# FW_Toolboard1_v71_Eagle_9.net
KiCad netlist of a schematic drawn in EAGLE
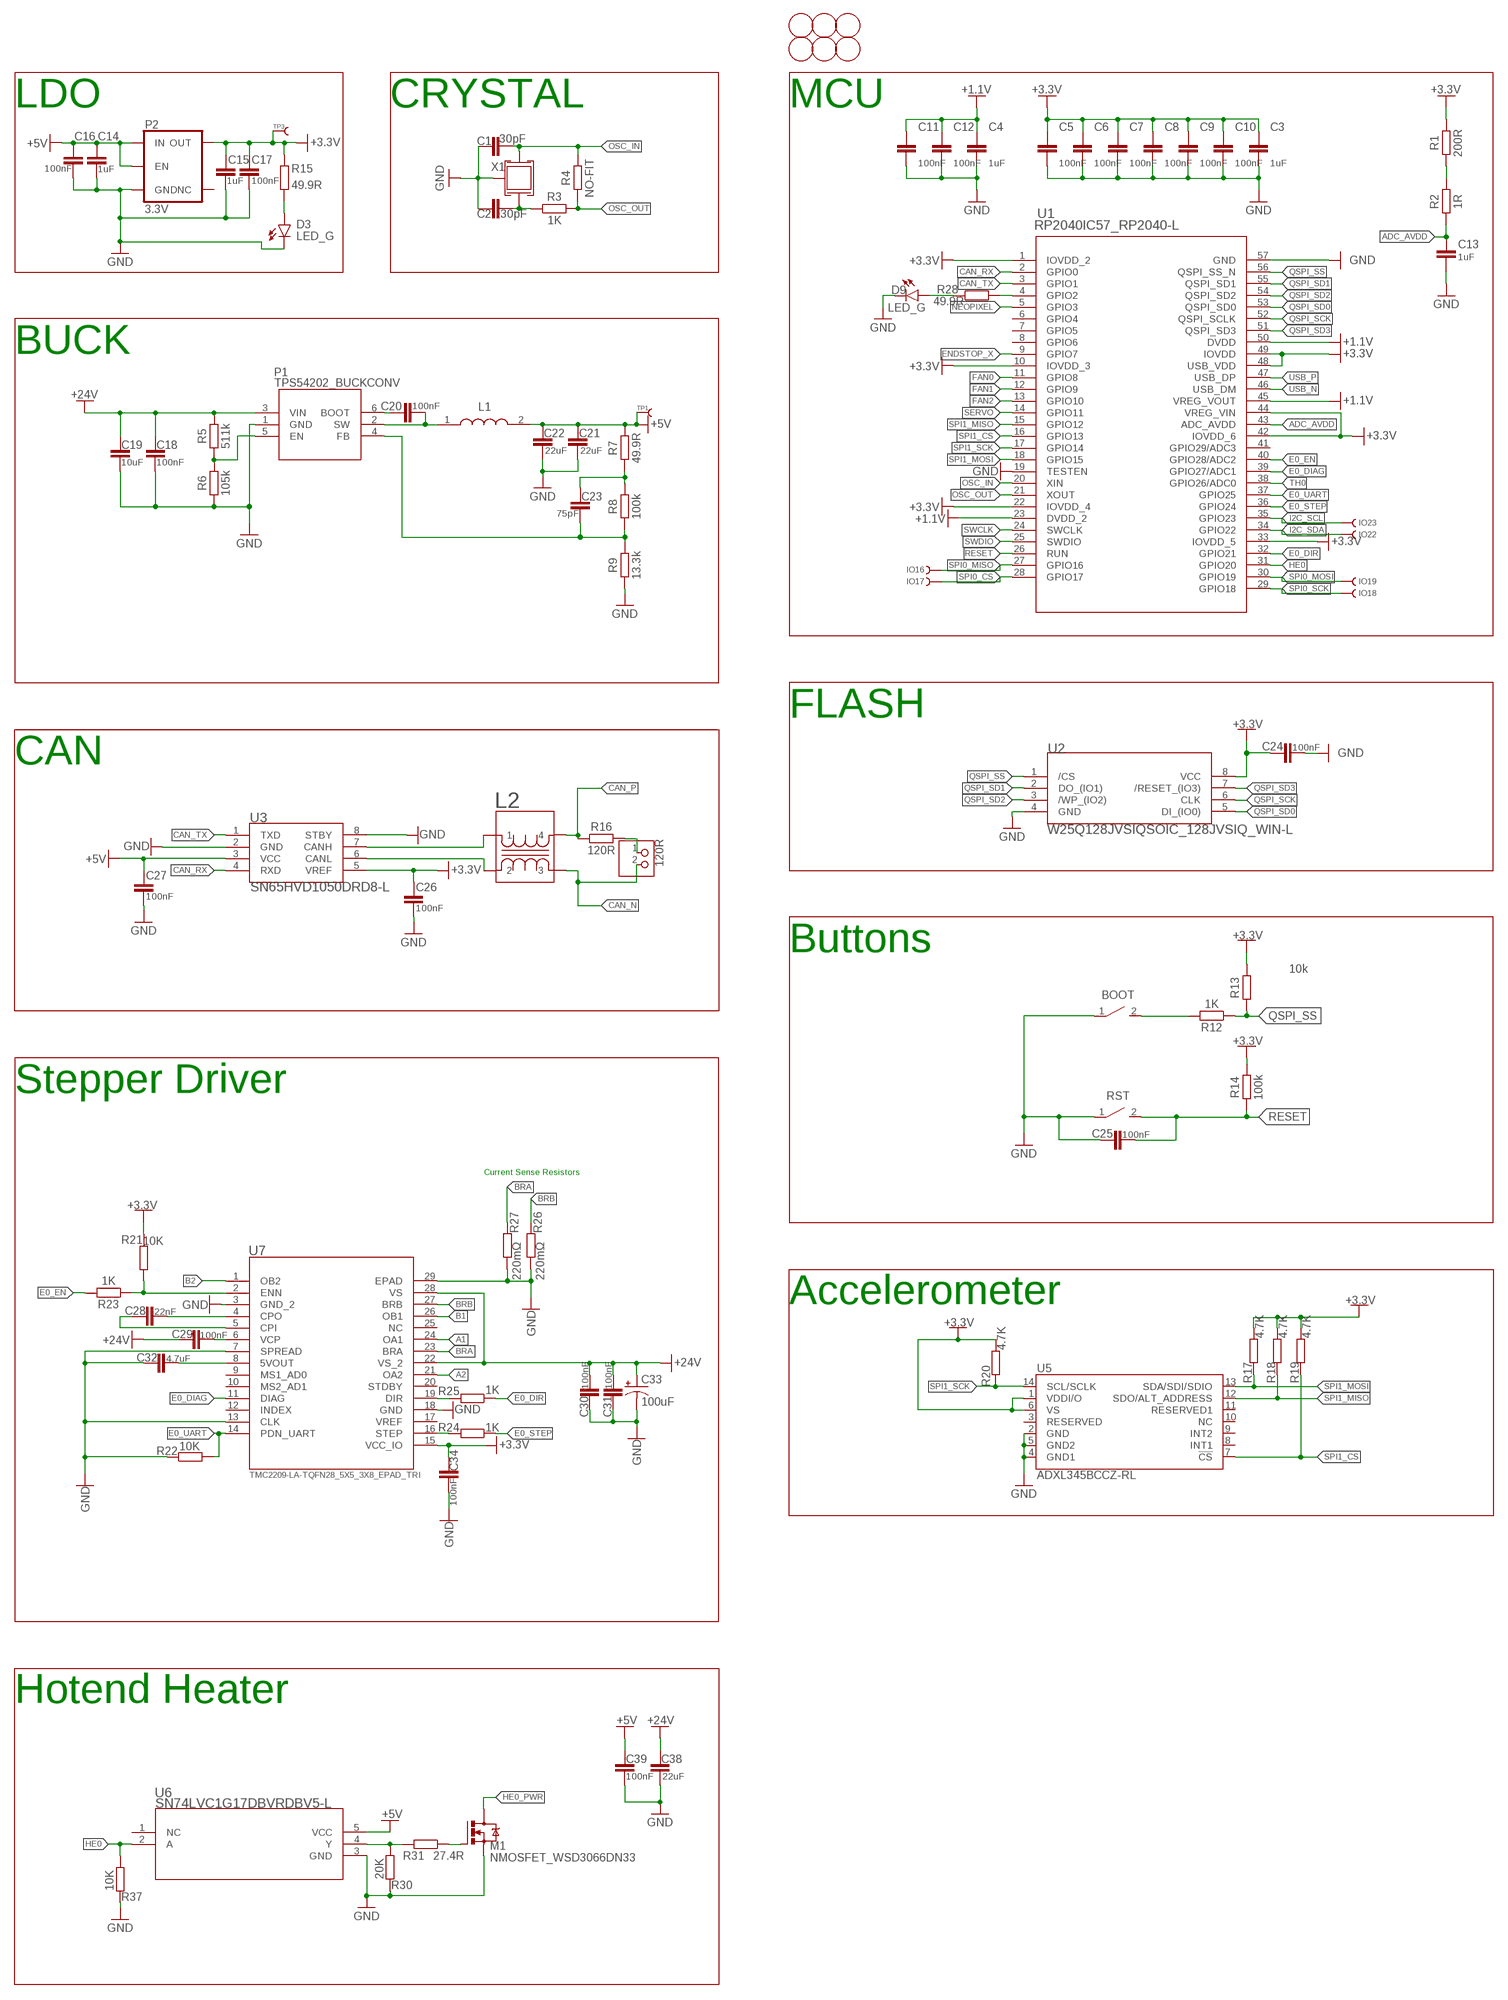
[diagram p0: schematic, sheet 1, part 1 of 2]
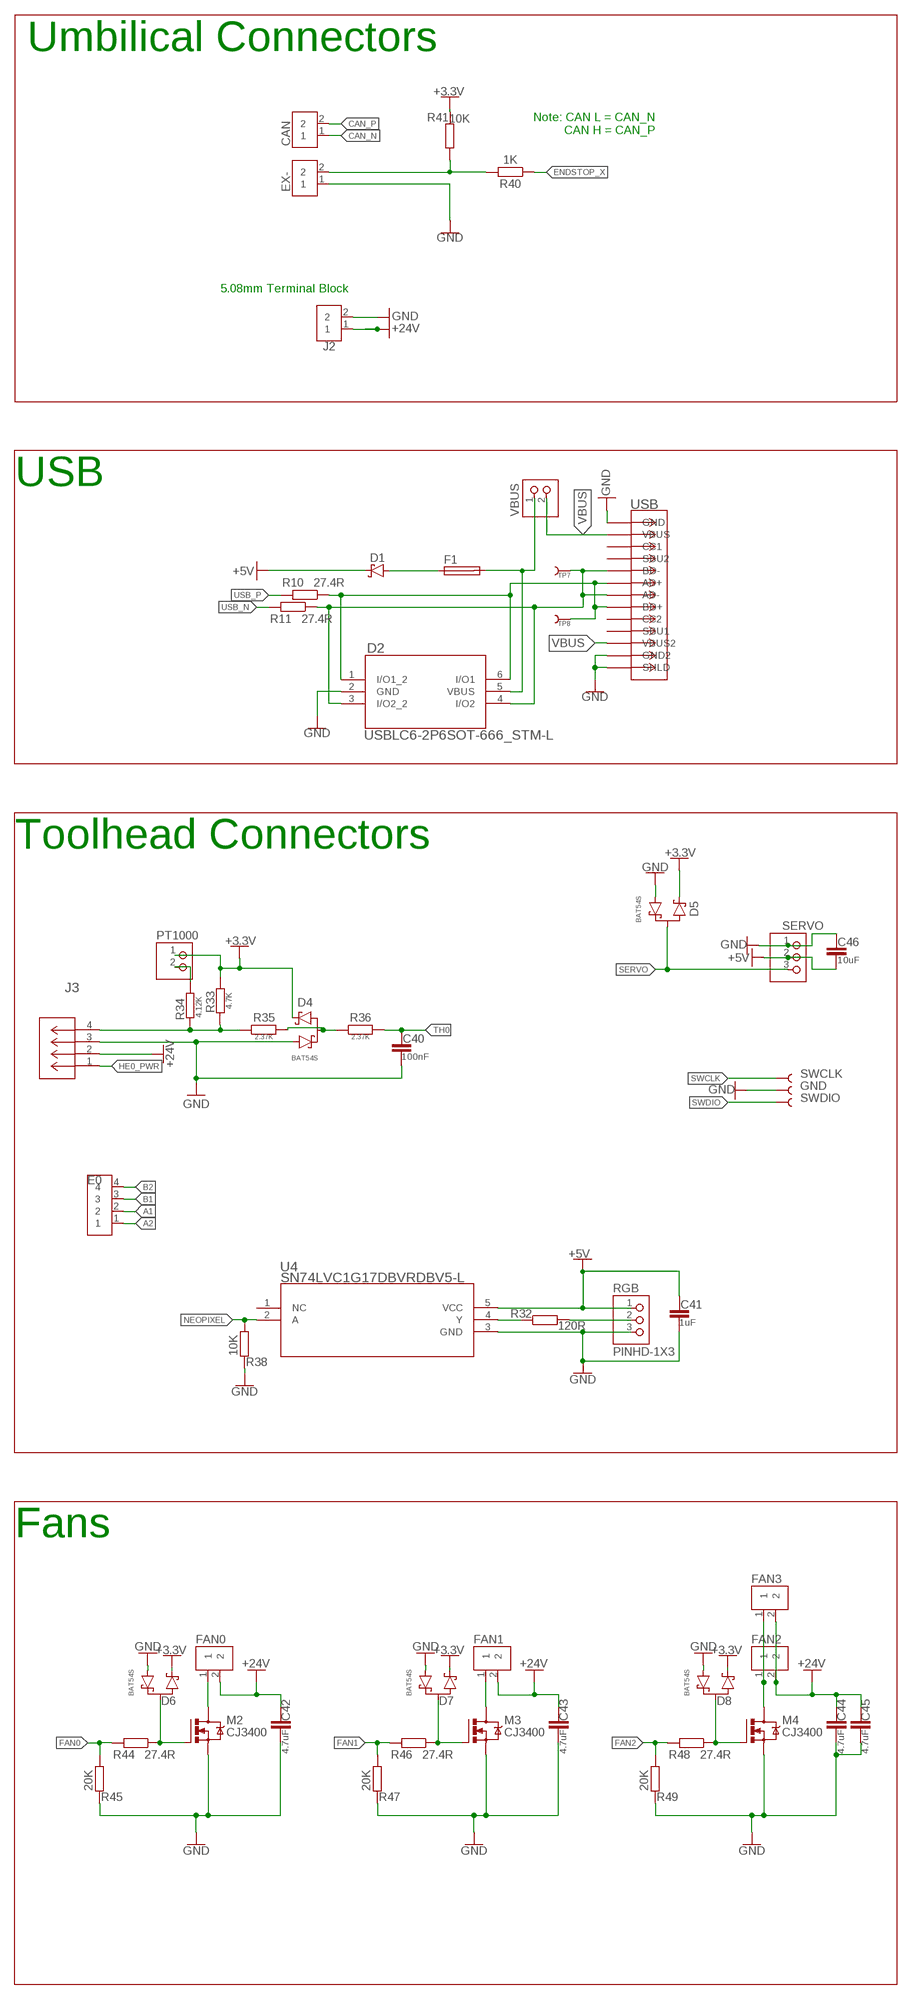
[diagram p1: schematic, sheet 1, part 2 of 2]

(export (version "E")
  (design (tool "Eeschema 10.0.6"))
  (components
    (comp (ref "120R")
      (value "PINHD-1X2")
      (footprint "eagle-import:1X02")
      (libsource (lib "eagle-import") (part "PINHD-1X2"))
    )
    (comp (ref "BOOT")
      (value "B3U-1000P(M)-B")
      (footprint "eagle-import:B3U-1000P(M)-B")
      (fields (field (name "MANUFACTURER") "OMRON"))
      (libsource (lib "eagle-import") (part "B3U-X0001000P(M)-BB3U-1000P(M)-B"))
    )
    (comp (ref "C1")
      (value "30pF")
      (footprint "eagle-import:CAPC1005X60")
      (libsource (lib "eagle-import") (part "CCHIP-0402(1005-METRIC)_"))
    )
    (comp (ref "C2")
      (value "30pF")
      (footprint "eagle-import:CAPC1005X60")
      (libsource (lib "eagle-import") (part "CCHIP-0402(1005-METRIC)_"))
    )
    (comp (ref "C3")
      (value "1uF")
      (footprint "eagle-import:CAPC1005X60")
      (libsource (lib "eagle-import") (part "CCHIP-0402(1005-METRIC)_"))
    )
    (comp (ref "C4")
      (value "1uF")
      (footprint "eagle-import:CAPC1005X60")
      (libsource (lib "eagle-import") (part "CCHIP-0402(1005-METRIC)_"))
    )
    (comp (ref "C5")
      (value "100nF")
      (footprint "eagle-import:CAPC1005X60")
      (libsource (lib "eagle-import") (part "CCHIP-0402(1005-METRIC)_"))
    )
    (comp (ref "C6")
      (value "100nF")
      (footprint "eagle-import:CAPC1005X60")
      (libsource (lib "eagle-import") (part "CCHIP-0402(1005-METRIC)_"))
    )
    (comp (ref "C7")
      (value "100nF")
      (footprint "eagle-import:CAPC1005X60")
      (libsource (lib "eagle-import") (part "CCHIP-0402(1005-METRIC)_"))
    )
    (comp (ref "C8")
      (value "100nF")
      (footprint "eagle-import:CAPC1005X60")
      (libsource (lib "eagle-import") (part "CCHIP-0402(1005-METRIC)_"))
    )
    (comp (ref "C9")
      (value "100nF")
      (footprint "eagle-import:CAPC1005X60")
      (libsource (lib "eagle-import") (part "CCHIP-0402(1005-METRIC)_"))
    )
    (comp (ref "C10")
      (value "100nF")
      (footprint "eagle-import:CAPC1005X60")
      (libsource (lib "eagle-import") (part "CCHIP-0402(1005-METRIC)_"))
    )
    (comp (ref "C11")
      (value "100nF")
      (footprint "eagle-import:CAPC1005X60")
      (libsource (lib "eagle-import") (part "CCHIP-0402(1005-METRIC)_"))
    )
    (comp (ref "C12")
      (value "100nF")
      (footprint "eagle-import:CAPC1005X60")
      (libsource (lib "eagle-import") (part "CCHIP-0402(1005-METRIC)_"))
    )
    (comp (ref "C13")
      (value "1uF")
      (footprint "eagle-import:CAPC1005X60")
      (libsource (lib "eagle-import") (part "CCHIP-0402(1005-METRIC)_"))
    )
    (comp (ref "C14")
      (value "1uF")
      (footprint "eagle-import:CAPC1005X60")
      (libsource (lib "eagle-import") (part "CCHIP-0402(1005-METRIC)_"))
    )
    (comp (ref "C15")
      (value "1uF")
      (footprint "eagle-import:CAPC1005X60")
      (libsource (lib "eagle-import") (part "CCHIP-0402(1005-METRIC)_"))
    )
    (comp (ref "C16")
      (value "100nF")
      (footprint "eagle-import:CAPC1005X60")
      (libsource (lib "eagle-import") (part "CCHIP-0402(1005-METRIC)_"))
    )
    (comp (ref "C17")
      (value "100nF")
      (footprint "eagle-import:CAPC1005X60")
      (libsource (lib "eagle-import") (part "CCHIP-0402(1005-METRIC)_"))
    )
    (comp (ref "C18")
      (value "100nF")
      (footprint "eagle-import:CAPC1005X60")
      (libsource (lib "eagle-import") (part "CCHIP-0402(1005-METRIC)_"))
    )
    (comp (ref "C19")
      (value "10uF")
      (footprint "eagle-import:CAPC1608X85")
      (libsource (lib "eagle-import") (part "CCHIP-0603(1608-METRIC)_"))
    )
    (comp (ref "C20")
      (value "100nF")
      (footprint "eagle-import:CAPC1005X60")
      (libsource (lib "eagle-import") (part "CCHIP-0402(1005-METRIC)_"))
    )
    (comp (ref "C21")
      (value "22uF")
      (footprint "eagle-import:CAPC2012X110")
      (libsource (lib "eagle-import") (part "CCHIP-0805(2012-METRIC)_"))
    )
    (comp (ref "C22")
      (value "22uF")
      (footprint "eagle-import:CAPC2012X110")
      (libsource (lib "eagle-import") (part "CCHIP-0805(2012-METRIC)_"))
    )
    (comp (ref "C23")
      (value "75pF")
      (footprint "eagle-import:CAPC1005X60")
      (libsource (lib "eagle-import") (part "CCHIP-0402(1005-METRIC)_"))
    )
    (comp (ref "C24")
      (value "100nF")
      (footprint "eagle-import:CAPC1005X60")
      (libsource (lib "eagle-import") (part "CCHIP-0402(1005-METRIC)_"))
    )
    (comp (ref "C25")
      (value "100nF")
      (footprint "eagle-import:CAPC1005X60")
      (libsource (lib "eagle-import") (part "CCHIP-0402(1005-METRIC)_"))
    )
    (comp (ref "C26")
      (value "100nF")
      (footprint "eagle-import:CAPC1005X60")
      (libsource (lib "eagle-import") (part "CCHIP-0402(1005-METRIC)_"))
    )
    (comp (ref "C27")
      (value "100nF")
      (footprint "eagle-import:CAPC1005X60")
      (libsource (lib "eagle-import") (part "CCHIP-0402(1005-METRIC)_"))
    )
    (comp (ref "C28")
      (value "22nF")
      (footprint "eagle-import:CAPC1005X60")
      (libsource (lib "eagle-import") (part "CCHIP-0402(1005-METRIC)_"))
    )
    (comp (ref "C29")
      (value "100nF")
      (footprint "eagle-import:CAPC1005X60")
      (libsource (lib "eagle-import") (part "CCHIP-0402(1005-METRIC)_"))
    )
    (comp (ref "C30")
      (value "100nF")
      (footprint "eagle-import:CAPC1005X60")
      (libsource (lib "eagle-import") (part "CCHIP-0402(1005-METRIC)_"))
    )
    (comp (ref "C31")
      (value "100nF")
      (footprint "eagle-import:CAPC1005X60")
      (libsource (lib "eagle-import") (part "CCHIP-0402(1005-METRIC)_"))
    )
    (comp (ref "C32")
      (value "4.7uF")
      (footprint "eagle-import:CAPC1608X85")
      (libsource (lib "eagle-import") (part "CCHIP-0603(1608-METRIC)_"))
    )
    (comp (ref "C33")
      (value "100uF")
      (footprint "eagle-import:PANASONIC_D")
      (libsource (lib "eagle-import") (part "100UF-POLAR-25V-20%(ELEC)"))
    )
    (comp (ref "C34")
      (value "100nF")
      (footprint "eagle-import:CAPC1005X60")
      (libsource (lib "eagle-import") (part "CCHIP-0402(1005-METRIC)_"))
    )
    (comp (ref "C38")
      (value "22uF")
      (footprint "eagle-import:CAPC2012X110")
      (libsource (lib "eagle-import") (part "CCHIP-0805(2012-METRIC)_"))
    )
    (comp (ref "C39")
      (value "100nF")
      (footprint "eagle-import:CAPC1005X60")
      (libsource (lib "eagle-import") (part "CCHIP-0402(1005-METRIC)_"))
    )
    (comp (ref "C40")
      (value "100nF")
      (footprint "eagle-import:CAPC1005X60")
      (libsource (lib "eagle-import") (part "CCHIP-0402(1005-METRIC)_"))
    )
    (comp (ref "C41")
      (value "1uF")
      (footprint "eagle-import:CAPC1005X60")
      (libsource (lib "eagle-import") (part "CCHIP-0402(1005-METRIC)_"))
    )
    (comp (ref "C42")
      (value "4.7uF")
      (footprint "eagle-import:CAPC1608X85")
      (libsource (lib "eagle-import") (part "CCHIP-0603(1608-METRIC)_"))
    )
    (comp (ref "C43")
      (value "4.7uF")
      (footprint "eagle-import:CAPC1608X85")
      (libsource (lib "eagle-import") (part "CCHIP-0603(1608-METRIC)_"))
    )
    (comp (ref "C44")
      (value "4.7uF")
      (footprint "eagle-import:CAPC1608X85")
      (libsource (lib "eagle-import") (part "CCHIP-0603(1608-METRIC)_"))
    )
    (comp (ref "C45")
      (value "4.7uF")
      (footprint "eagle-import:CAPC1608X85")
      (libsource (lib "eagle-import") (part "CCHIP-0603(1608-METRIC)_"))
    )
    (comp (ref "C46")
      (value "10uF")
      (footprint "eagle-import:CAPC1608X85")
      (libsource (lib "eagle-import") (part "CCHIP-0603(1608-METRIC)_"))
    )
    (comp (ref "CAN")
      (value "3A/250V")
      (footprint "eagle-import:S2B-XH-A")
      (fields
        (field (name "DIGIKEY_PART_NUMBER") "455-2257-ND")
        (field (name "MANUFACTURER") "JST Sales America Inc.")
        (field (name "MPN") "S2B-XH-A(LF)(SN)")
        (field (name "CREATED_BY") "PCBLayout.com")
      )
      (libsource (lib "eagle-import") (part "S2B-XH-A"))
    )
    (comp (ref "D1")
      (value "MBR0520LT1G")
      (footprint "eagle-import:SODFL3718X115")
      (fields (field (name "MANUFACTURER") "ON Semiconductor"))
      (libsource (lib "eagle-import") (part "SCHOTTKY_DO-219MBR0520LT1G"))
    )
    (comp (ref "D2")
      (value "USBLC6-2P6SOT-666_STM-L")
      (footprint "eagle-import:SOT-666_STM-L")
      (fields
        (field (name "MANUFACTURER_PART_NUMBER") "USBLC6-2P6")
        (field (name "COPYRIGHT") "Copyright (C) 2023 Ultra Librarian. All rights reserved.")
      )
      (libsource (lib "eagle-import") (part "USBLC6-2P6SOT-666_STM-L"))
    )
    (comp (ref "D3")
      (value "LED_G")
      (footprint "eagle-import:LEDC1608X35N_FLAT-G")
      (libsource (lib "eagle-import") (part "CHIP-FLAT-G_0603-0.35MM"))
    )
    (comp (ref "D4")
      (value "BAT54S")
      (footprint "eagle-import:SOT23")
      (libsource (lib "eagle-import") (part "BAT54S"))
    )
    (comp (ref "D5")
      (value "BAT54S")
      (footprint "eagle-import:SOT23")
      (libsource (lib "eagle-import") (part "BAT54S"))
    )
    (comp (ref "D6")
      (value "BAT54S")
      (footprint "eagle-import:SOT23")
      (libsource (lib "eagle-import") (part "BAT54S"))
    )
    (comp (ref "D7")
      (value "BAT54S")
      (footprint "eagle-import:SOT23")
      (libsource (lib "eagle-import") (part "BAT54S"))
    )
    (comp (ref "D8")
      (value "BAT54S")
      (footprint "eagle-import:SOT23")
      (libsource (lib "eagle-import") (part "BAT54S"))
    )
    (comp (ref "D9")
      (value "LED_G")
      (footprint "eagle-import:LEDC1608X35N_FLAT-G")
      (libsource (lib "eagle-import") (part "CHIP-FLAT-G_0603-0.35MM"))
    )
    (comp (ref "E0")
      (value "3A/250V")
      (footprint "eagle-import:S4B-XH-A")
      (fields (field (name "MANUFACTURER") "JST Sales America Inc. ") (field (name "MPN") "S4B-XH-A(LF)(SN)"))
      (libsource (lib "eagle-import") (part "S4B-XH-A"))
    )
    (comp (ref "EX-")
      (value "3A/250V")
      (footprint "eagle-import:S2B-XH-A")
      (fields
        (field (name "DIGIKEY_PART_NUMBER") "455-2257-ND")
        (field (name "MANUFACTURER") "JST Sales America Inc.")
        (field (name "MPN") "S2B-XH-A(LF)(SN)")
        (field (name "CREATED_BY") "PCBLayout.com")
      )
      (libsource (lib "eagle-import") (part "S2B-XH-A"))
    )
    (comp (ref "F1")
      (value "FUSE_CHIP-0603(1608-METRIC)")
      (footprint "eagle-import:FUSC1608X60N")
      (libsource (lib "eagle-import") (part "FUSECHIP-0603(1608-METRIC)_"))
    )
    (comp (ref "FAN0")
      (value "3A/250V")
      (footprint "eagle-import:S2B-XH-A")
      (fields
        (field (name "DIGIKEY_PART_NUMBER") "455-2257-ND")
        (field (name "MANUFACTURER") "JST Sales America Inc.")
        (field (name "MPN") "S2B-XH-A(LF)(SN)")
        (field (name "CREATED_BY") "PCBLayout.com")
      )
      (libsource (lib "eagle-import") (part "S2B-XH-A"))
    )
    (comp (ref "FAN1")
      (value "3A/250V")
      (footprint "eagle-import:S2B-XH-A")
      (fields
        (field (name "DIGIKEY_PART_NUMBER") "455-2257-ND")
        (field (name "MANUFACTURER") "JST Sales America Inc.")
        (field (name "MPN") "S2B-XH-A(LF)(SN)")
        (field (name "CREATED_BY") "PCBLayout.com")
      )
      (libsource (lib "eagle-import") (part "S2B-XH-A"))
    )
    (comp (ref "FAN2")
      (value "3A/250V")
      (footprint "eagle-import:S2B-XH-A")
      (fields
        (field (name "DIGIKEY_PART_NUMBER") "455-2257-ND")
        (field (name "MANUFACTURER") "JST Sales America Inc.")
        (field (name "MPN") "S2B-XH-A(LF)(SN)")
        (field (name "CREATED_BY") "PCBLayout.com")
      )
      (libsource (lib "eagle-import") (part "S2B-XH-A"))
    )
    (comp (ref "FAN3")
      (value "3A/250V")
      (footprint "eagle-import:S2B-XH-A")
      (fields
        (field (name "DIGIKEY_PART_NUMBER") "455-2257-ND")
        (field (name "MANUFACTURER") "JST Sales America Inc.")
        (field (name "MPN") "S2B-XH-A(LF)(SN)")
        (field (name "CREATED_BY") "PCBLayout.com")
      )
      (libsource (lib "eagle-import") (part "S2B-XH-A"))
    )
    (comp (ref "FD1")
      (value "FIDUCIAL")
      (footprint "eagle-import:FIDUCIAL_1MM")
      (libsource (lib "eagle-import") (part "FIDUCIAL"))
    )
    (comp (ref "FD2")
      (value "FIDUCIAL")
      (footprint "eagle-import:FIDUCIAL_1MM")
      (libsource (lib "eagle-import") (part "FIDUCIAL"))
    )
    (comp (ref "FD3")
      (value "FIDUCIAL")
      (footprint "eagle-import:FIDUCIAL_1MM")
      (libsource (lib "eagle-import") (part "FIDUCIAL"))
    )
    (comp (ref "FD4")
      (value "FIDUCIAL")
      (footprint "eagle-import:FIDUCIAL_1MM")
      (libsource (lib "eagle-import") (part "FIDUCIAL"))
    )
    (comp (ref "FD5")
      (value "FIDUCIAL")
      (footprint "eagle-import:FIDUCIAL_1MM")
      (libsource (lib "eagle-import") (part "FIDUCIAL"))
    )
    (comp (ref "FD6")
      (value "FIDUCIAL")
      (footprint "eagle-import:FIDUCIAL_1MM")
      (libsource (lib "eagle-import") (part "FIDUCIAL"))
    )
    (comp (ref "GND")
      (value "TEST-POINT3X4")
      (footprint "eagle-import:PAD.03X.04")
      (libsource (lib "eagle-import") (part "SparkFun-Connectors_513_TEST-POINT3X4"))
    )
    (comp (ref "IO16")
      (value "TEST-POINT3")
      (footprint "eagle-import:PAD.03X.03")
      (libsource (lib "eagle-import") (part "SparkFun-Connectors_513_TEST-POINT3"))
    )
    (comp (ref "IO17")
      (value "TEST-POINT3")
      (footprint "eagle-import:PAD.03X.03")
      (libsource (lib "eagle-import") (part "SparkFun-Connectors_513_TEST-POINT3"))
    )
    (comp (ref "IO18")
      (value "TEST-POINT3")
      (footprint "eagle-import:PAD.03X.03")
      (libsource (lib "eagle-import") (part "SparkFun-Connectors_513_TEST-POINT3"))
    )
    (comp (ref "IO19")
      (value "TEST-POINT3")
      (footprint "eagle-import:PAD.03X.03")
      (libsource (lib "eagle-import") (part "SparkFun-Connectors_513_TEST-POINT3"))
    )
    (comp (ref "IO22")
      (value "TEST-POINT3")
      (footprint "eagle-import:PAD.03X.03")
      (libsource (lib "eagle-import") (part "SparkFun-Connectors_513_TEST-POINT3"))
    )
    (comp (ref "IO23")
      (value "TEST-POINT3")
      (footprint "eagle-import:PAD.03X.03")
      (libsource (lib "eagle-import") (part "SparkFun-Connectors_513_TEST-POINT3"))
    )
    (comp (ref "J2")
      (value "2828XX-2282837-2")
      (footprint "eagle-import:TERMBLK_508-2N")
      (fields (field (name "MANUFACTURER") "TE Connectivity") (field (name "MPN") "282837-2"))
      (libsource (lib "eagle-import") (part "2828XX-2282837-2"))
    )
    (comp (ref "J3")
      (value "430450400CON_430450400_MOL")
      (footprint "eagle-import:CON_430450400_MOL")
      (fields
        (field (name "MANUFACTURER_PART_NUMBER") "430450400")
        (field (name "COPYRIGHT") "Copyright (C) 2023 Ultra Librarian. All rights reserved.")
      )
      (libsource (lib "eagle-import") (part "430450400CON_430450400_MOL"))
    )
    (comp (ref "L1")
      (value "ASPI-0630HI-100M-T157X7X4")
      (footprint "eagle-import:SMDRI74-680MT")
      (libsource (lib "eagle-import") (part "ASPI-0630HI-100M-T157X7X4"))
    )
    (comp (ref "L2")
      (value "ACM2012-201-2P-T002ACM2012_TDK")
      (footprint "eagle-import:ACM2012_TDK")
      (fields
        (field (name "MANUFACTURER_PART_NUMBER") "ACM2012-201-2P-T002")
        (field (name "COPYRIGHT") "Copyright (C) 2023 Ultra Librarian. All rights reserved.")
      )
      (libsource (lib "eagle-import") (part "ACM2012-201-2P-T002ACM2012_TDK"))
    )
    (comp (ref "M1")
      (value "NMOSFET_WSD3066DN33")
      (footprint "eagle-import:NMOSFET_WSD3066DN33")
      (libsource (lib "eagle-import") (part "NMOSFET_WSD3066DN33"))
    )
    (comp (ref "M2")
      (value "CJ3400")
      (footprint "eagle-import:SOT23")
      (fields (field (name "MANUFACTURER") "ON Semiconductor") (field (name "MPN") "BSS123L"))
      (libsource (lib "eagle-import") (part "NMOSFET__SOT23-GSDBSS123"))
    )
    (comp (ref "M3")
      (value "CJ3400")
      (footprint "eagle-import:SOT23")
      (fields (field (name "MANUFACTURER") "ON Semiconductor") (field (name "MPN") "BSS123L"))
      (libsource (lib "eagle-import") (part "NMOSFET__SOT23-GSDBSS123"))
    )
    (comp (ref "M4")
      (value "CJ3400")
      (footprint "eagle-import:SOT23")
      (fields (field (name "MANUFACTURER") "ON Semiconductor") (field (name "MPN") "BSS123L"))
      (libsource (lib "eagle-import") (part "NMOSFET__SOT23-GSDBSS123"))
    )
    (comp (ref "P1")
      (value "TPS54202_BUCKCONV")
      (footprint "eagle-import:SOT-23-6")
      (libsource (lib "eagle-import") (part "TPS54202_BUCKCONV"))
    )
    (comp (ref "P2")
      (value "3.3V")
      (footprint "eagle-import:SOT23-5")
      (libsource (lib "eagle-import") (part "V_REG_AP2112K-3.3V"))
    )
    (comp (ref "PT1000")
      (value "PINHD-1X2")
      (footprint "eagle-import:1X02")
      (libsource (lib "eagle-import") (part "PINHD-1X2"))
    )
    (comp (ref "R1")
      (value "200R")
      (footprint "eagle-import:RESC1005X40")
      (libsource (lib "eagle-import") (part "RCHIP-0402(1005-METRIC)_"))
    )
    (comp (ref "R2")
      (value "1R")
      (footprint "eagle-import:RESC1005X40")
      (libsource (lib "eagle-import") (part "RCHIP-0402(1005-METRIC)_"))
    )
    (comp (ref "R3")
      (value "1K")
      (footprint "eagle-import:RESC1005X40")
      (libsource (lib "eagle-import") (part "RCHIP-0402(1005-METRIC)_"))
    )
    (comp (ref "R4")
      (value "NO-FIT")
      (footprint "eagle-import:RESC1005X40")
      (libsource (lib "eagle-import") (part "RCHIP-0402(1005-METRIC)_"))
    )
    (comp (ref "R5")
      (value "511k")
      (footprint "eagle-import:RESC1005X40")
      (libsource (lib "eagle-import") (part "RCHIP-0402(1005-METRIC)_"))
    )
    (comp (ref "R6")
      (value "105k")
      (footprint "eagle-import:RESC1005X40")
      (libsource (lib "eagle-import") (part "RCHIP-0402(1005-METRIC)_"))
    )
    (comp (ref "R7")
      (value "49.9R")
      (footprint "eagle-import:RESC1005X40")
      (libsource (lib "eagle-import") (part "RCHIP-0402(1005-METRIC)_"))
    )
    (comp (ref "R8")
      (value "100k")
      (footprint "eagle-import:RESC1005X40")
      (libsource (lib "eagle-import") (part "RCHIP-0402(1005-METRIC)_"))
    )
    (comp (ref "R9")
      (value "13.3k")
      (footprint "eagle-import:RESC1005X40")
      (libsource (lib "eagle-import") (part "RCHIP-0402(1005-METRIC)_"))
    )
    (comp (ref "R10")
      (value "27.4R")
      (footprint "eagle-import:RESC1005X40")
      (libsource (lib "eagle-import") (part "RCHIP-0402(1005-METRIC)_"))
    )
    (comp (ref "R11")
      (value "27.4R")
      (footprint "eagle-import:RESC1005X40")
      (libsource (lib "eagle-import") (part "RCHIP-0402(1005-METRIC)_"))
    )
    (comp (ref "R12")
      (value "1K")
      (footprint "eagle-import:RESC1005X40")
      (libsource (lib "eagle-import") (part "RCHIP-0402(1005-METRIC)_"))
    )
    (comp (ref "R13")
      (value "10k")
      (footprint "eagle-import:RESC1005X40")
      (libsource (lib "eagle-import") (part "RCHIP-0402(1005-METRIC)_"))
    )
    (comp (ref "R14")
      (value "100k")
      (footprint "eagle-import:RESC1005X40")
      (libsource (lib "eagle-import") (part "RCHIP-0402(1005-METRIC)_"))
    )
    (comp (ref "R15")
      (value "49.9R")
      (footprint "eagle-import:RESC1005X40")
      (libsource (lib "eagle-import") (part "RCHIP-0402(1005-METRIC)_"))
    )
    (comp (ref "R16")
      (value "120R")
      (footprint "eagle-import:RESC1005X40")
      (libsource (lib "eagle-import") (part "RCHIP-0402(1005-METRIC)_"))
    )
    (comp (ref "R17")
      (value "4.7K")
      (footprint "eagle-import:RESC1005X40")
      (libsource (lib "eagle-import") (part "RCHIP-0402(1005-METRIC)_"))
    )
    (comp (ref "R18")
      (value "4.7K")
      (footprint "eagle-import:RESC1005X40")
      (libsource (lib "eagle-import") (part "RCHIP-0402(1005-METRIC)_"))
    )
    (comp (ref "R19")
      (value "4.7K")
      (footprint "eagle-import:RESC1005X40")
      (libsource (lib "eagle-import") (part "RCHIP-0402(1005-METRIC)_"))
    )
    (comp (ref "R20")
      (value "4.7K")
      (footprint "eagle-import:RESC1005X40")
      (libsource (lib "eagle-import") (part "RCHIP-0402(1005-METRIC)_"))
    )
    (comp (ref "R21")
      (value "10K")
      (footprint "eagle-import:RESC1005X40")
      (libsource (lib "eagle-import") (part "RCHIP-0402(1005-METRIC)_"))
    )
    (comp (ref "R22")
      (value "10K")
      (footprint "eagle-import:RESC1005X40")
      (libsource (lib "eagle-import") (part "RCHIP-0402(1005-METRIC)_"))
    )
    (comp (ref "R23")
      (value "1K")
      (footprint "eagle-import:RESC1005X40")
      (libsource (lib "eagle-import") (part "RCHIP-0402(1005-METRIC)_"))
    )
    (comp (ref "R24")
      (value "1K")
      (footprint "eagle-import:RESC1005X40")
      (libsource (lib "eagle-import") (part "RCHIP-0402(1005-METRIC)_"))
    )
    (comp (ref "R25")
      (value "1K")
      (footprint "eagle-import:RESC1005X40")
      (libsource (lib "eagle-import") (part "RCHIP-0402(1005-METRIC)_"))
    )
    (comp (ref "R26")
      (value "220mΩ")
      (footprint "eagle-import:RESC1005X40")
      (libsource (lib "eagle-import") (part "RCHIP-0402(1005-METRIC)_"))
    )
    (comp (ref "R27")
      (value "220mΩ")
      (footprint "eagle-import:RESC1005X40")
      (libsource (lib "eagle-import") (part "RCHIP-0402(1005-METRIC)_"))
    )
    (comp (ref "R28")
      (value "49.9R")
      (footprint "eagle-import:RESC1005X40")
      (libsource (lib "eagle-import") (part "RCHIP-0402(1005-METRIC)_"))
    )
    (comp (ref "R30")
      (value "20K")
      (footprint "eagle-import:RESC1005X40")
      (libsource (lib "eagle-import") (part "RCHIP-0402(1005-METRIC)_"))
    )
    (comp (ref "R31")
      (value "27.4R")
      (footprint "eagle-import:RESC1005X40")
      (libsource (lib "eagle-import") (part "RCHIP-0402(1005-METRIC)_"))
    )
    (comp (ref "R32")
      (value "120R")
      (footprint "eagle-import:RESC1005X40")
      (libsource (lib "eagle-import") (part "RCHIP-0402(1005-METRIC)_"))
    )
    (comp (ref "R33")
      (value "4.7K")
      (footprint "eagle-import:RESC1005X40")
      (libsource (lib "eagle-import") (part "RCHIP-0402(1005-METRIC)_"))
    )
    (comp (ref "R34")
      (value "4.12K")
      (footprint "eagle-import:RESC1005X40")
      (libsource (lib "eagle-import") (part "RCHIP-0402(1005-METRIC)_"))
    )
    (comp (ref "R35")
      (value "2.37K")
      (footprint "eagle-import:RESC1005X40")
      (libsource (lib "eagle-import") (part "RCHIP-0402(1005-METRIC)_"))
    )
    (comp (ref "R36")
      (value "2.37K")
      (footprint "eagle-import:RESC1005X40")
      (libsource (lib "eagle-import") (part "RCHIP-0402(1005-METRIC)_"))
    )
    (comp (ref "R37")
      (value "10K")
      (footprint "eagle-import:RESC1005X40")
      (libsource (lib "eagle-import") (part "RCHIP-0402(1005-METRIC)_"))
    )
    (comp (ref "R38")
      (value "10K")
      (footprint "eagle-import:RESC1005X40")
      (libsource (lib "eagle-import") (part "RCHIP-0402(1005-METRIC)_"))
    )
    (comp (ref "R40")
      (value "1K")
      (footprint "eagle-import:RESC1005X40")
      (libsource (lib "eagle-import") (part "RCHIP-0402(1005-METRIC)_"))
    )
    (comp (ref "R41")
      (value "10K")
      (footprint "eagle-import:RESC1005X40")
      (libsource (lib "eagle-import") (part "RCHIP-0402(1005-METRIC)_"))
    )
    (comp (ref "R44")
      (value "27.4R")
      (footprint "eagle-import:RESC1005X40")
      (libsource (lib "eagle-import") (part "RCHIP-0402(1005-METRIC)_"))
    )
    (comp (ref "R45")
      (value "20K")
      (footprint "eagle-import:RESC1005X40")
      (libsource (lib "eagle-import") (part "RCHIP-0402(1005-METRIC)_"))
    )
    (comp (ref "R46")
      (value "27.4R")
      (footprint "eagle-import:RESC1005X40")
      (libsource (lib "eagle-import") (part "RCHIP-0402(1005-METRIC)_"))
    )
    (comp (ref "R47")
      (value "20K")
      (footprint "eagle-import:RESC1005X40")
      (libsource (lib "eagle-import") (part "RCHIP-0402(1005-METRIC)_"))
    )
    (comp (ref "R48")
      (value "27.4R")
      (footprint "eagle-import:RESC1005X40")
      (libsource (lib "eagle-import") (part "RCHIP-0402(1005-METRIC)_"))
    )
    (comp (ref "R49")
      (value "20K")
      (footprint "eagle-import:RESC1005X40")
      (libsource (lib "eagle-import") (part "RCHIP-0402(1005-METRIC)_"))
    )
    (comp (ref "RGB")
      (value "PINHD-1X3")
      (footprint "eagle-import:1X03")
      (libsource (lib "eagle-import") (part "PINHD-1X3"))
    )
    (comp (ref "RST")
      (value "B3U-1000P(M)-B")
      (footprint "eagle-import:B3U-1000P(M)-B")
      (fields (field (name "MANUFACTURER") "OMRON"))
      (libsource (lib "eagle-import") (part "B3U-X0001000P(M)-BB3U-1000P(M)-B"))
    )
    (comp (ref "SERVO")
      (value "PINHD-1X3")
      (footprint "eagle-import:1X03")
      (libsource (lib "eagle-import") (part "PINHD-1X3"))
    )
    (comp (ref "SWCLK")
      (value "TEST-POINT3X4")
      (footprint "eagle-import:PAD.03X.04")
      (libsource (lib "eagle-import") (part "SparkFun-Connectors_513_TEST-POINT3X4"))
    )
    (comp (ref "SWDIO")
      (value "TEST-POINT3X4")
      (footprint "eagle-import:PAD.03X.04")
      (libsource (lib "eagle-import") (part "SparkFun-Connectors_513_TEST-POINT3X4"))
    )
    (comp (ref "TP1")
      (value "TEST-POINT3")
      (footprint "eagle-import:PAD.012X.012")
      (libsource (lib "eagle-import") (part "TEST-POINT3"))
    )
    (comp (ref "TP3")
      (value "TEST-POINT3")
      (footprint "eagle-import:PAD.012X.012")
      (libsource (lib "eagle-import") (part "TEST-POINT3"))
    )
    (comp (ref "TP7")
      (value "TEST-POINT3")
      (footprint "eagle-import:PAD.012X.012")
      (libsource (lib "eagle-import") (part "TEST-POINT3"))
    )
    (comp (ref "TP8")
      (value "TEST-POINT3")
      (footprint "eagle-import:PAD.012X.012")
      (libsource (lib "eagle-import") (part "TEST-POINT3"))
    )
    (comp (ref "U1")
      (value "RP2040IC57_RP2040-L")
      (footprint "eagle-import:IC57_RP2040-L")
      (fields
        (field (name "MANUFACTURER_PART_NUMBER") "RP2040")
        (field (name "COPYRIGHT") "Copyright (C) 2023 Ultra Librarian. All rights reserved.")
      )
      (libsource (lib "eagle-import") (part "RP2040IC57_RP2040-L"))
    )
    (comp (ref "U2")
      (value "W25Q128JVSIQSOIC_128JVSIQ_WIN-L")
      (footprint "eagle-import:SOIC_128JVSIQ_WIN-L")
      (fields
        (field (name "MANUFACTURER_PART_NUMBER") "W25Q128JVSIQ")
        (field (name "COPYRIGHT") "Copyright (C) 2023 Ultra Librarian. All rights reserved.")
      )
      (libsource (lib "eagle-import") (part "W25Q128JVSIQSOIC_128JVSIQ_WIN-L"))
    )
    (comp (ref "U3")
      (value "SN65HVD1050DRD8-L")
      (footprint "eagle-import:D8-L")
      (fields
        (field (name "MANUFACTURER_PART_NUMBER") "SN65HVD1050DR")
        (field (name "COPYRIGHT") "Copyright (C) 2023 Ultra Librarian. All rights reserved.")
      )
      (libsource (lib "eagle-import") (part "SN65HVD1050DRD8-L"))
    )
    (comp (ref "U4")
      (value "SN74LVC1G17DBVRDBV5-L")
      (footprint "eagle-import:DBV5-L")
      (fields
        (field (name "MANUFACTURER_PART_NUMBER") "SN74LVC1G17DBVR")
        (field (name "COPYRIGHT") "Copyright (C) 2023 Ultra Librarian. All rights reserved.")
      )
      (libsource (lib "eagle-import") (part "SN74LVC1G17DBVRDBV5-L"))
    )
    (comp (ref "U5")
      (value "ADXL345BCCZ-RL")
      (footprint "eagle-import:ADXL345_LGA14")
      (fields (field (name "MANUFACTURER") "ANALOG DEVICES"))
      (libsource (lib "eagle-import") (part "ADXL345BCCZ-RL"))
    )
    (comp (ref "U6")
      (value "SN74LVC1G17DBVRDBV5-L")
      (footprint "eagle-import:DBV5-L")
      (fields
        (field (name "MANUFACTURER_PART_NUMBER") "SN74LVC1G17DBVR")
        (field (name "COPYRIGHT") "Copyright (C) 2023 Ultra Librarian. All rights reserved.")
      )
      (libsource (lib "eagle-import") (part "SN74LVC1G17DBVRDBV5-L"))
    )
    (comp (ref "U7")
      (value "TMC2209-LA-TQFN28_5X5_3X8_EPAD_TRI")
      (footprint "eagle-import:QFN28_5X5_3X8_EPAD_TRI")
      (fields
        (field (name "MANUFACTURER_PART_NUMBER") "TMC2209-LA-T")
        (field (name "COPYRIGHT") "Copyright (C) 2023 Ultra Librarian. All rights reserved.")
      )
      (libsource (lib "eagle-import") (part "TMC2209-LA-TQFN28_5X5_3X8_EPAD_TRI"))
    )
    (comp (ref "USB")
      (value "USB-C(KH-TYPE-C-16P)")
      (footprint "eagle-import:CONN12_KH-TYPE-C-16P")
      (fields
        (field (name "MANUFACTURER_PART_NUMBER") "DX07S016JA1R1500")
        (field (name "VENDOR") "LCSC")
        (field (name "COPYRIGHT") "Copyright (C) 2018 Accelerated Designs. All rights reserved")
        (field (name "SOURCELIBRARY") "JAE_Electronics_2020-03-30")
      )
      (libsource (lib "eagle-import") (part "USB-C(KH-TYPE-C-16P)"))
    )
    (comp (ref "VBUS")
      (value "PINHD-1X2")
      (footprint "eagle-import:1X02")
      (libsource (lib "eagle-import") (part "PINHD-1X2"))
    )
    (comp (ref "X1")
      (value "CRYSTAL_TAXM12M4RLBDDT2T_3225")
      (footprint "eagle-import:CRYSTAL_3225")
      (libsource (lib "eagle-import") (part "CRYSTAL_TAXM12M4RLBDDT2T_3225"))
    )
  )
  (nets
    (net (code "1") (name "+1.1V") (class "Default")
      (node (ref "C11") (pin "1") (pinfunction "1_1") (pintype "passive"))
      (node (ref "C12") (pin "1") (pinfunction "1_1") (pintype "passive"))
      (node (ref "C4") (pin "1") (pinfunction "1_1") (pintype "passive"))
      (node (ref "U1") (pin "23") (pinfunction "DVDD_2_23") (pintype "power_in"))
      (node (ref "U1") (pin "45") (pinfunction "VREG_VOUT_45") (pintype "output"))
      (node (ref "U1") (pin "50") (pinfunction "DVDD_50") (pintype "power_in"))
    )
    (net (code "2") (name "+3.3V") (class "Default")
      (node (ref "C10") (pin "1") (pinfunction "1_1") (pintype "passive"))
      (node (ref "C15") (pin "1") (pinfunction "1_1") (pintype "passive"))
      (node (ref "C17") (pin "1") (pinfunction "1_1") (pintype "passive"))
      (node (ref "C24") (pin "1") (pinfunction "1_1") (pintype "passive"))
      (node (ref "C26") (pin "1") (pinfunction "1_1") (pintype "passive"))
      (node (ref "C3") (pin "1") (pinfunction "1_1") (pintype "passive"))
      (node (ref "C34") (pin "1") (pinfunction "1_1") (pintype "passive"))
      (node (ref "C5") (pin "1") (pinfunction "1_1") (pintype "passive"))
      (node (ref "C6") (pin "1") (pinfunction "1_1") (pintype "passive"))
      (node (ref "C7") (pin "1") (pinfunction "1_1") (pintype "passive"))
      (node (ref "C8") (pin "1") (pinfunction "1_1") (pintype "passive"))
      (node (ref "C9") (pin "1") (pinfunction "1_1") (pintype "passive"))
      (node (ref "D4") (pin "2") (pinfunction "2_2") (pintype "passive"))
      (node (ref "D5") (pin "2") (pinfunction "2_2") (pintype "passive"))
      (node (ref "D6") (pin "2") (pinfunction "2_2") (pintype "passive"))
      (node (ref "D7") (pin "2") (pinfunction "2_2") (pintype "passive"))
      (node (ref "D8") (pin "2") (pinfunction "2_2") (pintype "passive"))
      (node (ref "P2") (pin "5") (pinfunction "OUT_5") (pintype "passive"))
      (node (ref "PT1000") (pin "1") (pinfunction "1_1") (pintype "passive"))
      (node (ref "R1") (pin "2") (pinfunction "2_2") (pintype "passive"))
      (node (ref "R13") (pin "2") (pinfunction "2_2") (pintype "passive"))
      (node (ref "R14") (pin "2") (pinfunction "2_2") (pintype "passive"))
      (node (ref "R15") (pin "2") (pinfunction "2_2") (pintype "passive"))
      (node (ref "R17") (pin "2") (pinfunction "2_2") (pintype "passive"))
      (node (ref "R18") (pin "2") (pinfunction "2_2") (pintype "passive"))
      (node (ref "R19") (pin "2") (pinfunction "2_2") (pintype "passive"))
      (node (ref "R20") (pin "2") (pinfunction "2_2") (pintype "passive"))
      (node (ref "R21") (pin "1") (pinfunction "1_1") (pintype "passive"))
      (node (ref "R33") (pin "2") (pinfunction "2_2") (pintype "passive"))
      (node (ref "R41") (pin "1") (pinfunction "1_1") (pintype "passive"))
      (node (ref "TP3") (pin "P$1") (pinfunction "1_P$1") (pintype "bidirectional"))
      (node (ref "U1") (pin "1") (pinfunction "IOVDD_2_1") (pintype "power_in"))
      (node (ref "U1") (pin "10") (pinfunction "IOVDD_3_10") (pintype "power_in"))
      (node (ref "U1") (pin "22") (pinfunction "IOVDD_4_22") (pintype "power_in"))
      (node (ref "U1") (pin "33") (pinfunction "IOVDD_5_33") (pintype "power_in"))
      (node (ref "U1") (pin "42") (pinfunction "IOVDD_6_42") (pintype "power_in"))
      (node (ref "U1") (pin "44") (pinfunction "VREG_VIN_44") (pintype "passive"))
      (node (ref "U1") (pin "48") (pinfunction "USB_VDD_48") (pintype "power_in"))
      (node (ref "U1") (pin "49") (pinfunction "IOVDD_49") (pintype "power_in"))
      (node (ref "U2") (pin "8") (pinfunction "VCC_8") (pintype "power_in"))
      (node (ref "U3") (pin "5") (pinfunction "VREF_5") (pintype "power_in"))
      (node (ref "U5") (pin "1") (pinfunction "VDDI/O_1") (pintype "bidirectional"))
      (node (ref "U5") (pin "6") (pinfunction "VS_6") (pintype "bidirectional"))
      (node (ref "U7") (pin "15") (pinfunction "VCC_IO_15") (pintype "power_in"))
    )
    (net (code "3") (name "+5V") (class "Default")
      (node (ref "C14") (pin "1") (pinfunction "1_1") (pintype "passive"))
      (node (ref "C16") (pin "1") (pinfunction "1_1") (pintype "passive"))
      (node (ref "C21") (pin "1") (pinfunction "1_1") (pintype "passive"))
      (node (ref "C22") (pin "1") (pinfunction "1_1") (pintype "passive"))
      (node (ref "C27") (pin "1") (pinfunction "1_1") (pintype "passive"))
      (node (ref "C39") (pin "1") (pinfunction "1_1") (pintype "passive"))
      (node (ref "C41") (pin "1") (pinfunction "1_1") (pintype "passive"))
      (node (ref "C46") (pin "2") (pinfunction "2_2") (pintype "passive"))
      (node (ref "D1") (pin "1") (pinfunction "C_1") (pintype "passive"))
      (node (ref "L1") (pin "2") (pinfunction "2_2") (pintype "bidirectional"))
      (node (ref "P2") (pin "1") (pinfunction "IN_1") (pintype "input"))
      (node (ref "P2") (pin "3") (pinfunction "EN_3") (pintype "input"))
      (node (ref "R7") (pin "2") (pinfunction "2_2") (pintype "passive"))
      (node (ref "RGB") (pin "1") (pinfunction "1_1") (pintype "passive"))
      (node (ref "SERVO") (pin "2") (pinfunction "2_2") (pintype "passive"))
      (node (ref "TP1") (pin "P$1") (pinfunction "1_P$1") (pintype "bidirectional"))
      (node (ref "U3") (pin "3") (pinfunction "VCC_3") (pintype "power_in"))
      (node (ref "U4") (pin "5") (pinfunction "VCC_5") (pintype "power_in"))
      (node (ref "U6") (pin "5") (pinfunction "VCC_5") (pintype "power_in"))
    )
    (net (code "4") (name "+24V") (class "Default")
      (node (ref "C18") (pin "1") (pinfunction "1_1") (pintype "passive"))
      (node (ref "C19") (pin "1") (pinfunction "1_1") (pintype "passive"))
      (node (ref "C29") (pin "1") (pinfunction "1_1") (pintype "passive"))
      (node (ref "C30") (pin "2") (pinfunction "2_2") (pintype "passive"))
      (node (ref "C31") (pin "2") (pinfunction "2_2") (pintype "passive"))
      (node (ref "C33") (pin "+") (pinfunction "+_+") (pintype "passive"))
      (node (ref "C38") (pin "1") (pinfunction "1_1") (pintype "passive"))
      (node (ref "C42") (pin "1") (pinfunction "1_1") (pintype "passive"))
      (node (ref "C43") (pin "1") (pinfunction "1_1") (pintype "passive"))
      (node (ref "C44") (pin "1") (pinfunction "1_1") (pintype "passive"))
      (node (ref "C45") (pin "1") (pinfunction "1_1") (pintype "passive"))
      (node (ref "FAN0") (pin "2") (pinfunction "2_2") (pintype "bidirectional"))
      (node (ref "FAN1") (pin "2") (pinfunction "2_2") (pintype "bidirectional"))
      (node (ref "FAN2") (pin "2") (pinfunction "2_2") (pintype "bidirectional"))
      (node (ref "FAN3") (pin "2") (pinfunction "2_2") (pintype "bidirectional"))
      (node (ref "J2") (pin "1") (pinfunction "1_1") (pintype "bidirectional"))
      (node (ref "J3") (pin "2") (pinfunction "2_2") (pintype "passive"))
      (node (ref "P1") (pin "3") (pinfunction "VIN_3") (pintype "bidirectional"))
      (node (ref "R5") (pin "2") (pinfunction "2_2") (pintype "passive"))
      (node (ref "U7") (pin "22") (pinfunction "VS_2_22") (pintype "power_in"))
      (node (ref "U7") (pin "28") (pinfunction "VS_28") (pintype "power_in"))
    )
    (net (code "5") (name "A1") (class "Default")
      (node (ref "E0") (pin "2") (pinfunction "2_2") (pintype "bidirectional"))
      (node (ref "U7") (pin "24") (pinfunction "OA1_24") (pintype "output"))
    )
    (net (code "6") (name "A2") (class "Default")
      (node (ref "E0") (pin "1") (pinfunction "1_1") (pintype "bidirectional"))
      (node (ref "U7") (pin "21") (pinfunction "OA2_21") (pintype "output"))
    )
    (net (code "7") (name "ADC_AVDD") (class "Default")
      (node (ref "C13") (pin "1") (pinfunction "1_1") (pintype "passive"))
      (node (ref "R2") (pin "1") (pinfunction "1_1") (pintype "passive"))
      (node (ref "U1") (pin "43") (pinfunction "ADC_AVDD_43") (pintype "power_in"))
    )
    (net (code "8") (name "B1") (class "Default")
      (node (ref "E0") (pin "3") (pinfunction "3_3") (pintype "bidirectional"))
      (node (ref "U7") (pin "26") (pinfunction "OB1_26") (pintype "output"))
    )
    (net (code "9") (name "B2") (class "Default")
      (node (ref "E0") (pin "4") (pinfunction "4_4") (pintype "bidirectional"))
      (node (ref "U7") (pin "1") (pinfunction "OB2_1") (pintype "output"))
    )
    (net (code "10") (name "BRA") (class "Default")
      (node (ref "R27") (pin "2") (pinfunction "2_2") (pintype "passive"))
      (node (ref "U7") (pin "23") (pinfunction "BRA_23") (pintype "passive"))
    )
    (net (code "11") (name "BRB") (class "Default")
      (node (ref "R26") (pin "2") (pinfunction "2_2") (pintype "passive"))
      (node (ref "U7") (pin "27") (pinfunction "BRB_27") (pintype "passive"))
    )
    (net (code "12") (name "CAN_N") (class "Default")
      (node (ref "120R") (pin "2") (pinfunction "2_2") (pintype "passive"))
      (node (ref "CAN") (pin "1") (pinfunction "1_1") (pintype "bidirectional"))
      (node (ref "L2") (pin "3") (pinfunction "3_3") (pintype "passive"))
    )
    (net (code "13") (name "CAN_P") (class "Default")
      (node (ref "CAN") (pin "2") (pinfunction "2_2") (pintype "bidirectional"))
      (node (ref "L2") (pin "4") (pinfunction "4_4") (pintype "passive"))
      (node (ref "R16") (pin "1") (pinfunction "1_1") (pintype "passive"))
    )
    (net (code "14") (name "CAN_RX") (class "Default")
      (node (ref "U1") (pin "2") (pinfunction "GPIO0_2") (pintype "bidirectional"))
      (node (ref "U3") (pin "4") (pinfunction "RXD_4") (pintype "output"))
    )
    (net (code "15") (name "CAN_TX") (class "Default")
      (node (ref "U1") (pin "3") (pinfunction "GPIO1_3") (pintype "bidirectional"))
      (node (ref "U3") (pin "1") (pinfunction "TXD_1") (pintype "input"))
    )
    (net (code "16") (name "E0_DIAG") (class "Default")
      (node (ref "U1") (pin "39") (pinfunction "GPIO27/ADC1_39") (pintype "bidirectional"))
      (node (ref "U7") (pin "11") (pinfunction "DIAG_11") (pintype "output"))
    )
    (net (code "17") (name "E0_DIR") (class "Default")
      (node (ref "R25") (pin "1") (pinfunction "1_1") (pintype "passive"))
      (node (ref "U1") (pin "32") (pinfunction "GPIO21_32") (pintype "bidirectional"))
    )
    (net (code "18") (name "E0_EN") (class "Default")
      (node (ref "R23") (pin "2") (pinfunction "2_2") (pintype "passive"))
      (node (ref "U1") (pin "40") (pinfunction "GPIO28/ADC2_40") (pintype "bidirectional"))
    )
    (net (code "19") (name "E0_STEP") (class "Default")
      (node (ref "R24") (pin "1") (pinfunction "1_1") (pintype "passive"))
      (node (ref "U1") (pin "36") (pinfunction "GPIO24_36") (pintype "bidirectional"))
    )
    (net (code "20") (name "E0_UART") (class "Default")
      (node (ref "R22") (pin "2") (pinfunction "2_2") (pintype "passive"))
      (node (ref "U1") (pin "37") (pinfunction "GPIO25_37") (pintype "bidirectional"))
      (node (ref "U7") (pin "14") (pinfunction "PDN_UART_14") (pintype "bidirectional"))
    )
    (net (code "21") (name "ENDSTOP_X") (class "Default")
      (node (ref "R40") (pin "1") (pinfunction "1_1") (pintype "passive"))
      (node (ref "U1") (pin "9") (pinfunction "GPIO7_9") (pintype "bidirectional"))
    )
    (net (code "22") (name "FAN0") (class "Default")
      (node (ref "R44") (pin "2") (pinfunction "2_2") (pintype "passive"))
      (node (ref "R45") (pin "2") (pinfunction "2_2") (pintype "passive"))
      (node (ref "U1") (pin "11") (pinfunction "GPIO8_11") (pintype "bidirectional"))
    )
    (net (code "23") (name "FAN1") (class "Default")
      (node (ref "R46") (pin "2") (pinfunction "2_2") (pintype "passive"))
      (node (ref "R47") (pin "2") (pinfunction "2_2") (pintype "passive"))
      (node (ref "U1") (pin "12") (pinfunction "GPIO9_12") (pintype "bidirectional"))
    )
    (net (code "24") (name "FAN2") (class "Default")
      (node (ref "R48") (pin "2") (pinfunction "2_2") (pintype "passive"))
      (node (ref "R49") (pin "2") (pinfunction "2_2") (pintype "passive"))
      (node (ref "U1") (pin "13") (pinfunction "GPIO10_13") (pintype "bidirectional"))
    )
    (net (code "25") (name "GND") (class "Default")
      (node (ref "BOOT") (pin "1") (pinfunction "1_1") (pintype "bidirectional"))
      (node (ref "C1") (pin "2") (pinfunction "2_2") (pintype "passive"))
      (node (ref "C10") (pin "2") (pinfunction "2_2") (pintype "passive"))
      (node (ref "C11") (pin "2") (pinfunction "2_2") (pintype "passive"))
      (node (ref "C12") (pin "2") (pinfunction "2_2") (pintype "passive"))
      (node (ref "C13") (pin "2") (pinfunction "2_2") (pintype "passive"))
      (node (ref "C14") (pin "2") (pinfunction "2_2") (pintype "passive"))
      (node (ref "C15") (pin "2") (pinfunction "2_2") (pintype "passive"))
      (node (ref "C16") (pin "2") (pinfunction "2_2") (pintype "passive"))
      (node (ref "C17") (pin "2") (pinfunction "2_2") (pintype "passive"))
      (node (ref "C18") (pin "2") (pinfunction "2_2") (pintype "passive"))
      (node (ref "C19") (pin "2") (pinfunction "2_2") (pintype "passive"))
      (node (ref "C2") (pin "1") (pinfunction "1_1") (pintype "passive"))
      (node (ref "C21") (pin "2") (pinfunction "2_2") (pintype "passive"))
      (node (ref "C22") (pin "2") (pinfunction "2_2") (pintype "passive"))
      (node (ref "C24") (pin "2") (pinfunction "2_2") (pintype "passive"))
      (node (ref "C25") (pin "1") (pinfunction "1_1") (pintype "passive"))
      (node (ref "C26") (pin "2") (pinfunction "2_2") (pintype "passive"))
      (node (ref "C27") (pin "2") (pinfunction "2_2") (pintype "passive"))
      (node (ref "C3") (pin "2") (pinfunction "2_2") (pintype "passive"))
      (node (ref "C30") (pin "1") (pinfunction "1_1") (pintype "passive"))
      (node (ref "C31") (pin "1") (pinfunction "1_1") (pintype "passive"))
      (node (ref "C32") (pin "1") (pinfunction "1_1") (pintype "passive"))
      (node (ref "C33") (pin "-") (pinfunction "-_-") (pintype "passive"))
      (node (ref "C34") (pin "2") (pinfunction "2_2") (pintype "passive"))
      (node (ref "C38") (pin "2") (pinfunction "2_2") (pintype "passive"))
      (node (ref "C39") (pin "2") (pinfunction "2_2") (pintype "passive"))
      (node (ref "C4") (pin "2") (pinfunction "2_2") (pintype "passive"))
      (node (ref "C40") (pin "2") (pinfunction "2_2") (pintype "passive"))
      (node (ref "C41") (pin "2") (pinfunction "2_2") (pintype "passive"))
      (node (ref "C42") (pin "2") (pinfunction "2_2") (pintype "passive"))
      (node (ref "C43") (pin "2") (pinfunction "2_2") (pintype "passive"))
      (node (ref "C44") (pin "2") (pinfunction "2_2") (pintype "passive"))
      (node (ref "C45") (pin "2") (pinfunction "2_2") (pintype "passive"))
      (node (ref "C46") (pin "1") (pinfunction "1_1") (pintype "passive"))
      (node (ref "C5") (pin "2") (pinfunction "2_2") (pintype "passive"))
      (node (ref "C6") (pin "2") (pinfunction "2_2") (pintype "passive"))
      (node (ref "C7") (pin "2") (pinfunction "2_2") (pintype "passive"))
      (node (ref "C8") (pin "2") (pinfunction "2_2") (pintype "passive"))
      (node (ref "C9") (pin "2") (pinfunction "2_2") (pintype "passive"))
      (node (ref "D2") (pin "2") (pinfunction "GND_2") (pintype "power_in"))
      (node (ref "D3") (pin "C") (pinfunction "C_C") (pintype "passive"))
      (node (ref "D4") (pin "1") (pinfunction "1_1") (pintype "passive"))
      (node (ref "D5") (pin "1") (pinfunction "1_1") (pintype "passive"))
      (node (ref "D6") (pin "1") (pinfunction "1_1") (pintype "passive"))
      (node (ref "D7") (pin "1") (pinfunction "1_1") (pintype "passive"))
      (node (ref "D8") (pin "1") (pinfunction "1_1") (pintype "passive"))
      (node (ref "D9") (pin "C") (pinfunction "C_C") (pintype "passive"))
      (node (ref "EX-") (pin "1") (pinfunction "1_1") (pintype "bidirectional"))
      (node (ref "GND") (pin "P$1") (pinfunction "1_P$1") (pintype "bidirectional"))
      (node (ref "J2") (pin "2") (pinfunction "2_2") (pintype "bidirectional"))
      (node (ref "J3") (pin "3") (pinfunction "3_3") (pintype "passive"))
      (node (ref "M1") (pin "P$1") (pinfunction "S_P$1") (pintype "passive"))
      (node (ref "M1") (pin "P$2") (pinfunction "S_P$2") (pintype "passive"))
      (node (ref "M1") (pin "P$3") (pinfunction "S_P$3") (pintype "passive"))
      (node (ref "M2") (pin "2") (pinfunction "S_2") (pintype "passive"))
      (node (ref "M3") (pin "2") (pinfunction "S_2") (pintype "passive"))
      (node (ref "M4") (pin "2") (pinfunction "S_2") (pintype "passive"))
      (node (ref "P1") (pin "1") (pinfunction "GND_1") (pintype "bidirectional"))
      (node (ref "P2") (pin "2") (pinfunction "GND_2") (pintype "input"))
      (node (ref "R22") (pin "1") (pinfunction "1_1") (pintype "passive"))
      (node (ref "R26") (pin "1") (pinfunction "1_1") (pintype "passive"))
      (node (ref "R27") (pin "1") (pinfunction "1_1") (pintype "passive"))
      (node (ref "R30") (pin "1") (pinfunction "1_1") (pintype "passive"))
      (node (ref "R37") (pin "1") (pinfunction "1_1") (pintype "passive"))
      (node (ref "R38") (pin "1") (pinfunction "1_1") (pintype "passive"))
      (node (ref "R45") (pin "1") (pinfunction "1_1") (pintype "passive"))
      (node (ref "R47") (pin "1") (pinfunction "1_1") (pintype "passive"))
      (node (ref "R49") (pin "1") (pinfunction "1_1") (pintype "passive"))
      (node (ref "R6") (pin "1") (pinfunction "1_1") (pintype "passive"))
      (node (ref "R9") (pin "1") (pinfunction "1_1") (pintype "passive"))
      (node (ref "RGB") (pin "3") (pinfunction "3_3") (pintype "passive"))
      (node (ref "RST") (pin "1") (pinfunction "1_1") (pintype "bidirectional"))
      (node (ref "SERVO") (pin "1") (pinfunction "1_1") (pintype "passive"))
      (node (ref "U1") (pin "19") (pinfunction "TESTEN_19") (pintype "passive"))
      (node (ref "U1") (pin "57") (pinfunction "GND_57") (pintype "passive"))
      (node (ref "U2") (pin "4") (pinfunction "GND_4") (pintype "passive"))
      (node (ref "U3") (pin "2") (pinfunction "GND_2") (pintype "power_in"))
      (node (ref "U3") (pin "8") (pinfunction "STBY_8") (pintype "input"))
      (node (ref "U4") (pin "3") (pinfunction "GND_3") (pintype "power_in"))
      (node (ref "U5") (pin "2") (pinfunction "GND_2") (pintype "bidirectional"))
      (node (ref "U5") (pin "4") (pinfunction "GND1_4") (pintype "bidirectional"))
      (node (ref "U5") (pin "5") (pinfunction "GND2_5") (pintype "bidirectional"))
      (node (ref "U6") (pin "3") (pinfunction "GND_3") (pintype "power_in"))
      (node (ref "U7") (pin "13") (pinfunction "CLK_13") (pintype "input"))
      (node (ref "U7") (pin "18") (pinfunction "GND_18") (pintype "power_in"))
      (node (ref "U7") (pin "29") (pinfunction "EPAD_29") (pintype "passive"))
      (node (ref "U7") (pin "3") (pinfunction "GND_2_3") (pintype "power_in"))
      (node (ref "U7") (pin "7") (pinfunction "SPREAD_7") (pintype "input"))
      (node (ref "USB") (pin "1") (pinfunction "GND_1") (pintype "power_in"))
      (node (ref "USB") (pin "12") (pinfunction "GND2_12") (pintype "power_in"))
      (node (ref "USB") (pin "13") (pinfunction "SHLD_13") (pintype "passive"))
      (node (ref "USB") (pin "14") (pinfunction "SHLD_14") (pintype "passive"))
      (node (ref "USB") (pin "15") (pinfunction "SHLD_15") (pintype "passive"))
      (node (ref "USB") (pin "16") (pinfunction "SHLD_16") (pintype "passive"))
      (node (ref "USB") (pin "18") (pinfunction "SHLD_18") (pintype "passive"))
      (node (ref "USB") (pin "19") (pinfunction "SHLD_19") (pintype "passive"))
      (node (ref "USB") (pin "20") (pinfunction "SHLD_20") (pintype "passive"))
      (node (ref "USB") (pin "21") (pinfunction "SHLD_21") (pintype "passive"))
      (node (ref "USB") (pin "24") (pinfunction "SHLD_24") (pintype "passive"))
      (node (ref "USB") (pin "25") (pinfunction "SHLD_25") (pintype "passive"))
      (node (ref "USB") (pin "26") (pinfunction "SHLD_26") (pintype "passive"))
      (node (ref "USB") (pin "27") (pinfunction "SHLD_27") (pintype "passive"))
      (node (ref "USB") (pin "28") (pinfunction "SHLD_28") (pintype "passive"))
      (node (ref "USB") (pin "29") (pinfunction "SHLD_29") (pintype "passive"))
      (node (ref "USB") (pin "37") (pinfunction "SHLD_37") (pintype "passive"))
      (node (ref "USB") (pin "39") (pinfunction "SHLD_39") (pintype "passive"))
      (node (ref "USB") (pin "41") (pinfunction "SHLD_41") (pintype "passive"))
      (node (ref "USB") (pin "43") (pinfunction "SHLD_43") (pintype "passive"))
      (node (ref "X1") (pin "P$2") (pinfunction "GND_P$2") (pintype "bidirectional"))
      (node (ref "X1") (pin "P$4") (pinfunction "GND_P$4") (pintype "bidirectional"))
    )
    (net (code "26") (name "HE0") (class "Default")
      (node (ref "R37") (pin "2") (pinfunction "2_2") (pintype "passive"))
      (node (ref "U1") (pin "31") (pinfunction "GPIO20_31") (pintype "bidirectional"))
      (node (ref "U6") (pin "2") (pinfunction "A_2") (pintype "input"))
    )
    (net (code "27") (name "HE0_PWR") (class "Default")
      (node (ref "J3") (pin "1") (pinfunction "1_1") (pintype "passive"))
      (node (ref "M1") (pin "P$5") (pinfunction "D_P$5") (pintype "passive"))
      (node (ref "M1") (pin "P$6") (pinfunction "D_P$6") (pintype "passive"))
      (node (ref "M1") (pin "P$7") (pinfunction "D_P$7") (pintype "passive"))
      (node (ref "M1") (pin "P$8") (pinfunction "D_P$8") (pintype "passive"))
      (node (ref "M1") (pin "P$9") (pinfunction "D_P$9") (pintype "passive"))
    )
    (net (code "28") (name "I2C_SCL") (class "Default")
      (node (ref "IO23") (pin "P$1") (pinfunction "1_P$1") (pintype "bidirectional"))
      (node (ref "U1") (pin "35") (pinfunction "GPIO23_35") (pintype "bidirectional"))
    )
    (net (code "29") (name "I2C_SDA") (class "Default")
      (node (ref "IO22") (pin "P$1") (pinfunction "1_P$1") (pintype "bidirectional"))
      (node (ref "U1") (pin "34") (pinfunction "GPIO22_34") (pintype "bidirectional"))
    )
    (net (code "30") (name "NEOPIXEL") (class "Default")
      (node (ref "R38") (pin "2") (pinfunction "2_2") (pintype "passive"))
      (node (ref "U1") (pin "5") (pinfunction "GPIO3_5") (pintype "bidirectional"))
      (node (ref "U4") (pin "2") (pinfunction "A_2") (pintype "input"))
    )
    (net (code "31") (name "Net-(120R-Pad1)") (class "Default")
      (node (ref "120R") (pin "1") (pinfunction "1_1") (pintype "passive"))
      (node (ref "R16") (pin "2") (pinfunction "2_2") (pintype "passive"))
    )
    (net (code "32") (name "Net-(BOOT-Pad2)") (class "Default")
      (node (ref "BOOT") (pin "2") (pinfunction "2_2") (pintype "bidirectional"))
      (node (ref "R12") (pin "2") (pinfunction "2_2") (pintype "passive"))
    )
    (net (code "33") (name "Net-(C23-Pad1)") (class "Default")
      (node (ref "C23") (pin "1") (pinfunction "1_1") (pintype "passive"))
      (node (ref "R7") (pin "1") (pinfunction "1_1") (pintype "passive"))
      (node (ref "R8") (pin "2") (pinfunction "2_2") (pintype "passive"))
    )
    (net (code "34") (name "Net-(D1-A)") (class "Default")
      (node (ref "D1") (pin "2") (pinfunction "A_2") (pintype "passive"))
      (node (ref "F1") (pin "1") (pinfunction "1_1") (pintype "passive"))
    )
    (net (code "35") (name "Net-(D2-I{slash}O1)") (class "Default")
      (node (ref "D2") (pin "1") (pinfunction "I/O1_2_1") (pintype "bidirectional"))
      (node (ref "D2") (pin "6") (pinfunction "I/O1_6") (pintype "bidirectional"))
      (node (ref "R10") (pin "1") (pinfunction "1_1") (pintype "passive"))
      (node (ref "TP8") (pin "P$1") (pinfunction "1_P$1") (pintype "bidirectional"))
      (node (ref "USB") (pin "6") (pinfunction "AD+_6") (pintype "passive"))
      (node (ref "USB") (pin "8") (pinfunction "BD+_8") (pintype "passive"))
    )
    (net (code "36") (name "Net-(D2-I{slash}O2)") (class "Default")
      (node (ref "D2") (pin "3") (pinfunction "I/O2_2_3") (pintype "bidirectional"))
      (node (ref "D2") (pin "4") (pinfunction "I/O2_4") (pintype "bidirectional"))
      (node (ref "R11") (pin "1") (pinfunction "1_1") (pintype "passive"))
      (node (ref "TP7") (pin "P$1") (pinfunction "1_P$1") (pintype "bidirectional"))
      (node (ref "USB") (pin "5") (pinfunction "BD-_5") (pintype "passive"))
      (node (ref "USB") (pin "7") (pinfunction "AD-_7") (pintype "passive"))
    )
    (net (code "37") (name "Net-(D2-VBUS)") (class "Default")
      (node (ref "D2") (pin "5") (pinfunction "VBUS_5") (pintype "power_in"))
      (node (ref "F1") (pin "2") (pinfunction "2_2") (pintype "passive"))
      (node (ref "VBUS") (pin "1") (pinfunction "1_1") (pintype "passive"))
    )
    (net (code "38") (name "Net-(D3-PadA)") (class "Default")
      (node (ref "D3") (pin "A") (pinfunction "A_A") (pintype "passive"))
      (node (ref "R15") (pin "1") (pinfunction "1_1") (pintype "passive"))
    )
    (net (code "39") (name "Net-(D4-Pad3)") (class "Default")
      (node (ref "D4") (pin "3") (pinfunction "3_3") (pintype "passive"))
      (node (ref "R35") (pin "2") (pinfunction "2_2") (pintype "passive"))
      (node (ref "R36") (pin "1") (pinfunction "1_1") (pintype "passive"))
    )
    (net (code "40") (name "Net-(D9-PadA)") (class "Default")
      (node (ref "D9") (pin "A") (pinfunction "A_A") (pintype "passive"))
      (node (ref "R28") (pin "1") (pinfunction "1_1") (pintype "passive"))
    )
    (net (code "41") (name "Net-(EX--Pad2)") (class "Default")
      (node (ref "EX-") (pin "2") (pinfunction "2_2") (pintype "bidirectional"))
      (node (ref "R40") (pin "2") (pinfunction "2_2") (pintype "passive"))
      (node (ref "R41") (pin "2") (pinfunction "2_2") (pintype "passive"))
    )
    (net (code "42") (name "Net-(J3-Pad4)") (class "Default")
      (node (ref "J3") (pin "4") (pinfunction "4_4") (pintype "passive"))
      (node (ref "R33") (pin "1") (pinfunction "1_1") (pintype "passive"))
      (node (ref "R34") (pin "1") (pinfunction "1_1") (pintype "passive"))
      (node (ref "R35") (pin "1") (pinfunction "1_1") (pintype "passive"))
    )
    (net (code "43") (name "Net-(M1-G)") (class "Default")
      (node (ref "M1") (pin "P$4") (pinfunction "G_P$4") (pintype "passive"))
      (node (ref "R31") (pin "1") (pinfunction "1_1") (pintype "passive"))
    )
    (net (code "44") (name "Net-(M2-D)") (class "Default")
      (node (ref "FAN0") (pin "1") (pinfunction "1_1") (pintype "bidirectional"))
      (node (ref "M2") (pin "3") (pinfunction "D_3") (pintype "passive"))
    )
    (net (code "45") (name "Net-(M2-G)") (class "Default")
      (node (ref "D6") (pin "3") (pinfunction "3_3") (pintype "passive"))
      (node (ref "M2") (pin "1") (pinfunction "G_1") (pintype "passive"))
      (node (ref "R44") (pin "1") (pinfunction "1_1") (pintype "passive"))
    )
    (net (code "46") (name "Net-(M3-D)") (class "Default")
      (node (ref "FAN1") (pin "1") (pinfunction "1_1") (pintype "bidirectional"))
      (node (ref "M3") (pin "3") (pinfunction "D_3") (pintype "passive"))
    )
    (net (code "47") (name "Net-(M3-G)") (class "Default")
      (node (ref "D7") (pin "3") (pinfunction "3_3") (pintype "passive"))
      (node (ref "M3") (pin "1") (pinfunction "G_1") (pintype "passive"))
      (node (ref "R46") (pin "1") (pinfunction "1_1") (pintype "passive"))
    )
    (net (code "48") (name "Net-(M4-D)") (class "Default")
      (node (ref "FAN2") (pin "1") (pinfunction "1_1") (pintype "bidirectional"))
      (node (ref "FAN3") (pin "1") (pinfunction "1_1") (pintype "bidirectional"))
      (node (ref "M4") (pin "3") (pinfunction "D_3") (pintype "passive"))
    )
    (net (code "49") (name "Net-(M4-G)") (class "Default")
      (node (ref "D8") (pin "3") (pinfunction "3_3") (pintype "passive"))
      (node (ref "M4") (pin "1") (pinfunction "G_1") (pintype "passive"))
      (node (ref "R48") (pin "1") (pinfunction "1_1") (pintype "passive"))
    )
    (net (code "50") (name "Net-(P1-BOOT)") (class "Default")
      (node (ref "C20") (pin "1") (pinfunction "1_1") (pintype "passive"))
      (node (ref "P1") (pin "6") (pinfunction "BOOT_6") (pintype "bidirectional"))
    )
    (net (code "51") (name "Net-(P1-EN)") (class "Default")
      (node (ref "P1") (pin "5") (pinfunction "EN_5") (pintype "bidirectional"))
      (node (ref "R5") (pin "1") (pinfunction "1_1") (pintype "passive"))
      (node (ref "R6") (pin "2") (pinfunction "2_2") (pintype "passive"))
    )
    (net (code "52") (name "Net-(P1-FB)") (class "Default")
      (node (ref "C23") (pin "2") (pinfunction "2_2") (pintype "passive"))
      (node (ref "P1") (pin "4") (pinfunction "FB_4") (pintype "bidirectional"))
      (node (ref "R8") (pin "1") (pinfunction "1_1") (pintype "passive"))
      (node (ref "R9") (pin "2") (pinfunction "2_2") (pintype "passive"))
    )
    (net (code "53") (name "Net-(P1-SW)") (class "Default")
      (node (ref "C20") (pin "2") (pinfunction "2_2") (pintype "passive"))
      (node (ref "L1") (pin "1") (pinfunction "1_1") (pintype "bidirectional"))
      (node (ref "P1") (pin "2") (pinfunction "SW_2") (pintype "bidirectional"))
    )
    (net (code "54") (name "Net-(PT1000-Pad2)") (class "Default")
      (node (ref "PT1000") (pin "2") (pinfunction "2_2") (pintype "passive"))
      (node (ref "R34") (pin "2") (pinfunction "2_2") (pintype "passive"))
    )
    (net (code "55") (name "Net-(R1-Pad1)") (class "Default")
      (node (ref "R1") (pin "1") (pinfunction "1_1") (pintype "passive"))
      (node (ref "R2") (pin "2") (pinfunction "2_2") (pintype "passive"))
    )
    (net (code "56") (name "Net-(R32-Pad2)") (class "Default")
      (node (ref "R32") (pin "2") (pinfunction "2_2") (pintype "passive"))
      (node (ref "RGB") (pin "2") (pinfunction "2_2") (pintype "passive"))
    )
    (net (code "57") (name "Net-(U1-GPIO2)") (class "Default")
      (node (ref "R28") (pin "2") (pinfunction "2_2") (pintype "passive"))
      (node (ref "U1") (pin "4") (pinfunction "GPIO2_4") (pintype "bidirectional"))
    )
    (net (code "58") (name "Net-(U3-CANH)") (class "Default")
      (node (ref "L2") (pin "1") (pinfunction "1_1") (pintype "passive"))
      (node (ref "U3") (pin "7") (pinfunction "CANH_7") (pintype "output"))
    )
    (net (code "59") (name "Net-(U3-CANL)") (class "Default")
      (node (ref "L2") (pin "2") (pinfunction "2_2") (pintype "passive"))
      (node (ref "U3") (pin "6") (pinfunction "CANL_6") (pintype "output"))
    )
    (net (code "60") (name "Net-(U4-Y)") (class "Default")
      (node (ref "R32") (pin "1") (pinfunction "1_1") (pintype "passive"))
      (node (ref "U4") (pin "4") (pinfunction "Y_4") (pintype "output"))
    )
    (net (code "61") (name "Net-(U6-Y)") (class "Default")
      (node (ref "R30") (pin "2") (pinfunction "2_2") (pintype "passive"))
      (node (ref "R31") (pin "2") (pinfunction "2_2") (pintype "passive"))
      (node (ref "U6") (pin "4") (pinfunction "Y_4") (pintype "output"))
    )
    (net (code "62") (name "Net-(U7-5VOUT)") (class "Default")
      (node (ref "C32") (pin "2") (pinfunction "2_2") (pintype "passive"))
      (node (ref "U7") (pin "8") (pinfunction "5VOUT_8") (pintype "output"))
    )
    (net (code "63") (name "Net-(U7-CPI)") (class "Default")
      (node (ref "C28") (pin "1") (pinfunction "1_1") (pintype "passive"))
      (node (ref "U7") (pin "5") (pinfunction "CPI_5") (pintype "input"))
    )
    (net (code "64") (name "Net-(U7-CPO)") (class "Default")
      (node (ref "C28") (pin "2") (pinfunction "2_2") (pintype "passive"))
      (node (ref "U7") (pin "4") (pinfunction "CPO_4") (pintype "output"))
    )
    (net (code "65") (name "Net-(U7-DIR)") (class "Default")
      (node (ref "R25") (pin "2") (pinfunction "2_2") (pintype "passive"))
      (node (ref "U7") (pin "19") (pinfunction "DIR_19") (pintype "input"))
    )
    (net (code "66") (name "Net-(U7-ENN)") (class "Default")
      (node (ref "R21") (pin "2") (pinfunction "2_2") (pintype "passive"))
      (node (ref "R23") (pin "1") (pinfunction "1_1") (pintype "passive"))
      (node (ref "U7") (pin "2") (pinfunction "ENN_2") (pintype "input"))
    )
    (net (code "67") (name "Net-(U7-STEP)") (class "Default")
      (node (ref "R24") (pin "2") (pinfunction "2_2") (pintype "passive"))
      (node (ref "U7") (pin "16") (pinfunction "STEP_16") (pintype "input"))
    )
    (net (code "68") (name "Net-(U7-VCP)") (class "Default")
      (node (ref "C29") (pin "2") (pinfunction "2_2") (pintype "passive"))
      (node (ref "U7") (pin "6") (pinfunction "VCP_6") (pintype "power_in"))
    )
    (net (code "69") (name "Net-(X1-P2)") (class "Default")
      (node (ref "C2") (pin "2") (pinfunction "2_2") (pintype "passive"))
      (node (ref "R3") (pin "1") (pinfunction "1_1") (pintype "passive"))
      (node (ref "X1") (pin "P$3") (pinfunction "P2_P$3") (pintype "bidirectional"))
    )
    (net (code "70") (name "OSC_IN") (class "Default")
      (node (ref "C1") (pin "1") (pinfunction "1_1") (pintype "passive"))
      (node (ref "R4") (pin "2") (pinfunction "2_2") (pintype "passive"))
      (node (ref "U1") (pin "20") (pinfunction "XIN_20") (pintype "passive"))
      (node (ref "X1") (pin "P$1") (pinfunction "P1_P$1") (pintype "bidirectional"))
    )
    (net (code "71") (name "OSC_OUT") (class "Default")
      (node (ref "R3") (pin "2") (pinfunction "2_2") (pintype "passive"))
      (node (ref "R4") (pin "1") (pinfunction "1_1") (pintype "passive"))
      (node (ref "U1") (pin "21") (pinfunction "XOUT_21") (pintype "output"))
    )
    (net (code "72") (name "QSPI_SCK") (class "Default")
      (node (ref "U1") (pin "52") (pinfunction "QSPI_SCLK_52") (pintype "passive"))
      (node (ref "U2") (pin "6") (pinfunction "CLK_6") (pintype "passive"))
    )
    (net (code "73") (name "QSPI_SD0") (class "Default")
      (node (ref "U1") (pin "53") (pinfunction "QSPI_SD0_53") (pintype "bidirectional"))
      (node (ref "U2") (pin "5") (pinfunction "DI_(IO0)_5") (pintype "passive"))
    )
    (net (code "74") (name "QSPI_SD1") (class "Default")
      (node (ref "U1") (pin "55") (pinfunction "QSPI_SD1_55") (pintype "bidirectional"))
      (node (ref "U2") (pin "2") (pinfunction "DO_(IO1)_2") (pintype "passive"))
    )
    (net (code "75") (name "QSPI_SD2") (class "Default")
      (node (ref "U1") (pin "54") (pinfunction "QSPI_SD2_54") (pintype "bidirectional"))
      (node (ref "U2") (pin "3") (pinfunction "/WP_(IO2)_3") (pintype "passive"))
    )
    (net (code "76") (name "QSPI_SD3") (class "Default")
      (node (ref "U1") (pin "51") (pinfunction "QSPI_SD3_51") (pintype "bidirectional"))
      (node (ref "U2") (pin "7") (pinfunction "/RESET_(IO3)_7") (pintype "passive"))
    )
    (net (code "77") (name "QSPI_SS") (class "Default")
      (node (ref "R12") (pin "1") (pinfunction "1_1") (pintype "passive"))
      (node (ref "R13") (pin "1") (pinfunction "1_1") (pintype "passive"))
      (node (ref "U1") (pin "56") (pinfunction "QSPI_SS_N_56") (pintype "passive"))
      (node (ref "U2") (pin "1") (pinfunction "/CS_1") (pintype "passive"))
    )
    (net (code "78") (name "RESET") (class "Default")
      (node (ref "C25") (pin "2") (pinfunction "2_2") (pintype "passive"))
      (node (ref "R14") (pin "1") (pinfunction "1_1") (pintype "passive"))
      (node (ref "RST") (pin "2") (pinfunction "2_2") (pintype "bidirectional"))
      (node (ref "U1") (pin "26") (pinfunction "RUN_26") (pintype "passive"))
    )
    (net (code "79") (name "SERVO") (class "Default")
      (node (ref "D5") (pin "3") (pinfunction "3_3") (pintype "passive"))
      (node (ref "SERVO") (pin "3") (pinfunction "3_3") (pintype "passive"))
      (node (ref "U1") (pin "14") (pinfunction "GPIO11_14") (pintype "bidirectional"))
    )
    (net (code "80") (name "SPI0_CS") (class "Default")
      (node (ref "IO17") (pin "P$1") (pinfunction "1_P$1") (pintype "bidirectional"))
      (node (ref "U1") (pin "28") (pinfunction "GPIO17_28") (pintype "bidirectional"))
    )
    (net (code "81") (name "SPI0_MISO") (class "Default")
      (node (ref "IO16") (pin "P$1") (pinfunction "1_P$1") (pintype "bidirectional"))
      (node (ref "U1") (pin "27") (pinfunction "GPIO16_27") (pintype "bidirectional"))
    )
    (net (code "82") (name "SPI0_MOSI") (class "Default")
      (node (ref "IO19") (pin "P$1") (pinfunction "1_P$1") (pintype "bidirectional"))
      (node (ref "U1") (pin "30") (pinfunction "GPIO19_30") (pintype "bidirectional"))
    )
    (net (code "83") (name "SPI0_SCK") (class "Default")
      (node (ref "IO18") (pin "P$1") (pinfunction "1_P$1") (pintype "bidirectional"))
      (node (ref "U1") (pin "29") (pinfunction "GPIO18_29") (pintype "bidirectional"))
    )
    (net (code "84") (name "SPI1_CS") (class "Default")
      (node (ref "R19") (pin "1") (pinfunction "1_1") (pintype "passive"))
      (node (ref "U1") (pin "16") (pinfunction "GPIO13_16") (pintype "bidirectional"))
      (node (ref "U5") (pin "7") (pinfunction "~{CS}_7") (pintype "bidirectional"))
    )
    (net (code "85") (name "SPI1_MISO") (class "Default")
      (node (ref "R18") (pin "1") (pinfunction "1_1") (pintype "passive"))
      (node (ref "U1") (pin "15") (pinfunction "GPIO12_15") (pintype "bidirectional"))
      (node (ref "U5") (pin "12") (pinfunction "SDO/ALT_ADDRESS_12") (pintype "bidirectional"))
    )
    (net (code "86") (name "SPI1_MOSI") (class "Default")
      (node (ref "R17") (pin "1") (pinfunction "1_1") (pintype "passive"))
      (node (ref "U1") (pin "18") (pinfunction "GPIO15_18") (pintype "bidirectional"))
      (node (ref "U5") (pin "13") (pinfunction "SDA/SDI/SDIO_13") (pintype "bidirectional"))
    )
    (net (code "87") (name "SPI1_SCK") (class "Default")
      (node (ref "R20") (pin "1") (pinfunction "1_1") (pintype "passive"))
      (node (ref "U1") (pin "17") (pinfunction "GPIO14_17") (pintype "bidirectional"))
      (node (ref "U5") (pin "14") (pinfunction "SCL/SCLK_14") (pintype "bidirectional"))
    )
    (net (code "88") (name "SWCLK") (class "Default")
      (node (ref "SWCLK") (pin "P$1") (pinfunction "1_P$1") (pintype "bidirectional"))
      (node (ref "U1") (pin "24") (pinfunction "SWCLK_24") (pintype "passive"))
    )
    (net (code "89") (name "SWDIO") (class "Default")
      (node (ref "SWDIO") (pin "P$1") (pinfunction "1_P$1") (pintype "bidirectional"))
      (node (ref "U1") (pin "25") (pinfunction "SWDIO_25") (pintype "passive"))
    )
    (net (code "90") (name "TH0") (class "Default")
      (node (ref "C40") (pin "1") (pinfunction "1_1") (pintype "passive"))
      (node (ref "R36") (pin "2") (pinfunction "2_2") (pintype "passive"))
      (node (ref "U1") (pin "38") (pinfunction "GPIO26/ADC0_38") (pintype "bidirectional"))
    )
    (net (code "91") (name "USB_N") (class "Default")
      (node (ref "R11") (pin "2") (pinfunction "2_2") (pintype "passive"))
      (node (ref "U1") (pin "46") (pinfunction "USB_DM_46") (pintype "passive"))
    )
    (net (code "92") (name "USB_P") (class "Default")
      (node (ref "R10") (pin "2") (pinfunction "2_2") (pintype "passive"))
      (node (ref "U1") (pin "47") (pinfunction "USB_DP_47") (pintype "passive"))
    )
    (net (code "93") (name "VBUS") (class "Default")
      (node (ref "USB") (pin "11") (pinfunction "VBUS2_11") (pintype "power_in"))
      (node (ref "USB") (pin "2") (pinfunction "VBUS_2") (pintype "power_in"))
      (node (ref "VBUS") (pin "2") (pinfunction "2_2") (pintype "passive"))
    )
    (net (code "94") (name "unconnected-(P2-NC-Pad4)") (class "Default")
      (node (ref "P2") (pin "4") (pinfunction "NC_4") (pintype "no_connect"))
    )
    (net (code "95") (name "unconnected-(U1-GPIO4-Pad6)") (class "Default")
      (node (ref "U1") (pin "6") (pinfunction "GPIO4_6") (pintype "bidirectional"))
    )
    (net (code "96") (name "unconnected-(U1-GPIO5-Pad7)") (class "Default")
      (node (ref "U1") (pin "7") (pinfunction "GPIO5_7") (pintype "bidirectional"))
    )
    (net (code "97") (name "unconnected-(U1-GPIO6-Pad8)") (class "Default")
      (node (ref "U1") (pin "8") (pinfunction "GPIO6_8") (pintype "bidirectional"))
    )
    (net (code "98") (name "unconnected-(U1-GPIO29{slash}ADC3-Pad41)") (class "Default")
      (node (ref "U1") (pin "41") (pinfunction "GPIO29/ADC3_41") (pintype "bidirectional"))
    )
    (net (code "99") (name "unconnected-(U4-NC-Pad1)") (class "Default")
      (node (ref "U4") (pin "1") (pinfunction "NC_1") (pintype "passive"))
    )
    (net (code "100") (name "unconnected-(U5-INT1-Pad8)") (class "Default")
      (node (ref "U5") (pin "8") (pinfunction "INT1_8") (pintype "bidirectional"))
    )
    (net (code "101") (name "unconnected-(U5-INT2-Pad9)") (class "Default")
      (node (ref "U5") (pin "9") (pinfunction "INT2_9") (pintype "bidirectional"))
    )
    (net (code "102") (name "unconnected-(U5-NC-Pad10)") (class "Default")
      (node (ref "U5") (pin "10") (pinfunction "NC_10") (pintype "bidirectional"))
    )
    (net (code "103") (name "unconnected-(U5-RESERVED-Pad3)") (class "Default")
      (node (ref "U5") (pin "3") (pinfunction "RESERVED_3") (pintype "bidirectional"))
    )
    (net (code "104") (name "unconnected-(U5-RESERVED1-Pad11)") (class "Default")
      (node (ref "U5") (pin "11") (pinfunction "RESERVED1_11") (pintype "bidirectional"))
    )
    (net (code "105") (name "unconnected-(U6-NC-Pad1)") (class "Default")
      (node (ref "U6") (pin "1") (pinfunction "NC_1") (pintype "passive"))
    )
    (net (code "106") (name "unconnected-(U7-INDEX-Pad12)") (class "Default")
      (node (ref "U7") (pin "12") (pinfunction "INDEX_12") (pintype "output"))
    )
    (net (code "107") (name "unconnected-(U7-MS1_AD0-Pad9)") (class "Default")
      (node (ref "U7") (pin "9") (pinfunction "MS1_AD0_9") (pintype "input"))
    )
    (net (code "108") (name "unconnected-(U7-MS2_AD1-Pad10)") (class "Default")
      (node (ref "U7") (pin "10") (pinfunction "MS2_AD1_10") (pintype "input"))
    )
    (net (code "109") (name "unconnected-(U7-NC-Pad25)") (class "Default")
      (node (ref "U7") (pin "25") (pinfunction "NC_25") (pintype "no_connect"))
    )
    (net (code "110") (name "unconnected-(U7-STDBY-Pad20)") (class "Default")
      (node (ref "U7") (pin "20") (pinfunction "STDBY_20") (pintype "input"))
    )
    (net (code "111") (name "unconnected-(U7-VREF-Pad17)") (class "Default")
      (node (ref "U7") (pin "17") (pinfunction "VREF_17") (pintype "input"))
    )
    (net (code "112") (name "unconnected-(USB-CC1-Pad3)") (class "Default")
      (node (ref "USB") (pin "3") (pinfunction "CC1_3") (pintype "passive"))
    )
    (net (code "113") (name "unconnected-(USB-CC2-Pad9)") (class "Default")
      (node (ref "USB") (pin "9") (pinfunction "CC2_9") (pintype "passive"))
    )
    (net (code "114") (name "unconnected-(USB-SBU1-Pad10)") (class "Default")
      (node (ref "USB") (pin "10") (pinfunction "SBU1_10") (pintype "passive"))
    )
    (net (code "115") (name "unconnected-(USB-SBU2-Pad4)") (class "Default")
      (node (ref "USB") (pin "4") (pinfunction "SBU2_4") (pintype "passive"))
    )
  )
)
